# harp_timestamp_generator_Gen3.net
KiCad netlist of a schematic drawn in EAGLE
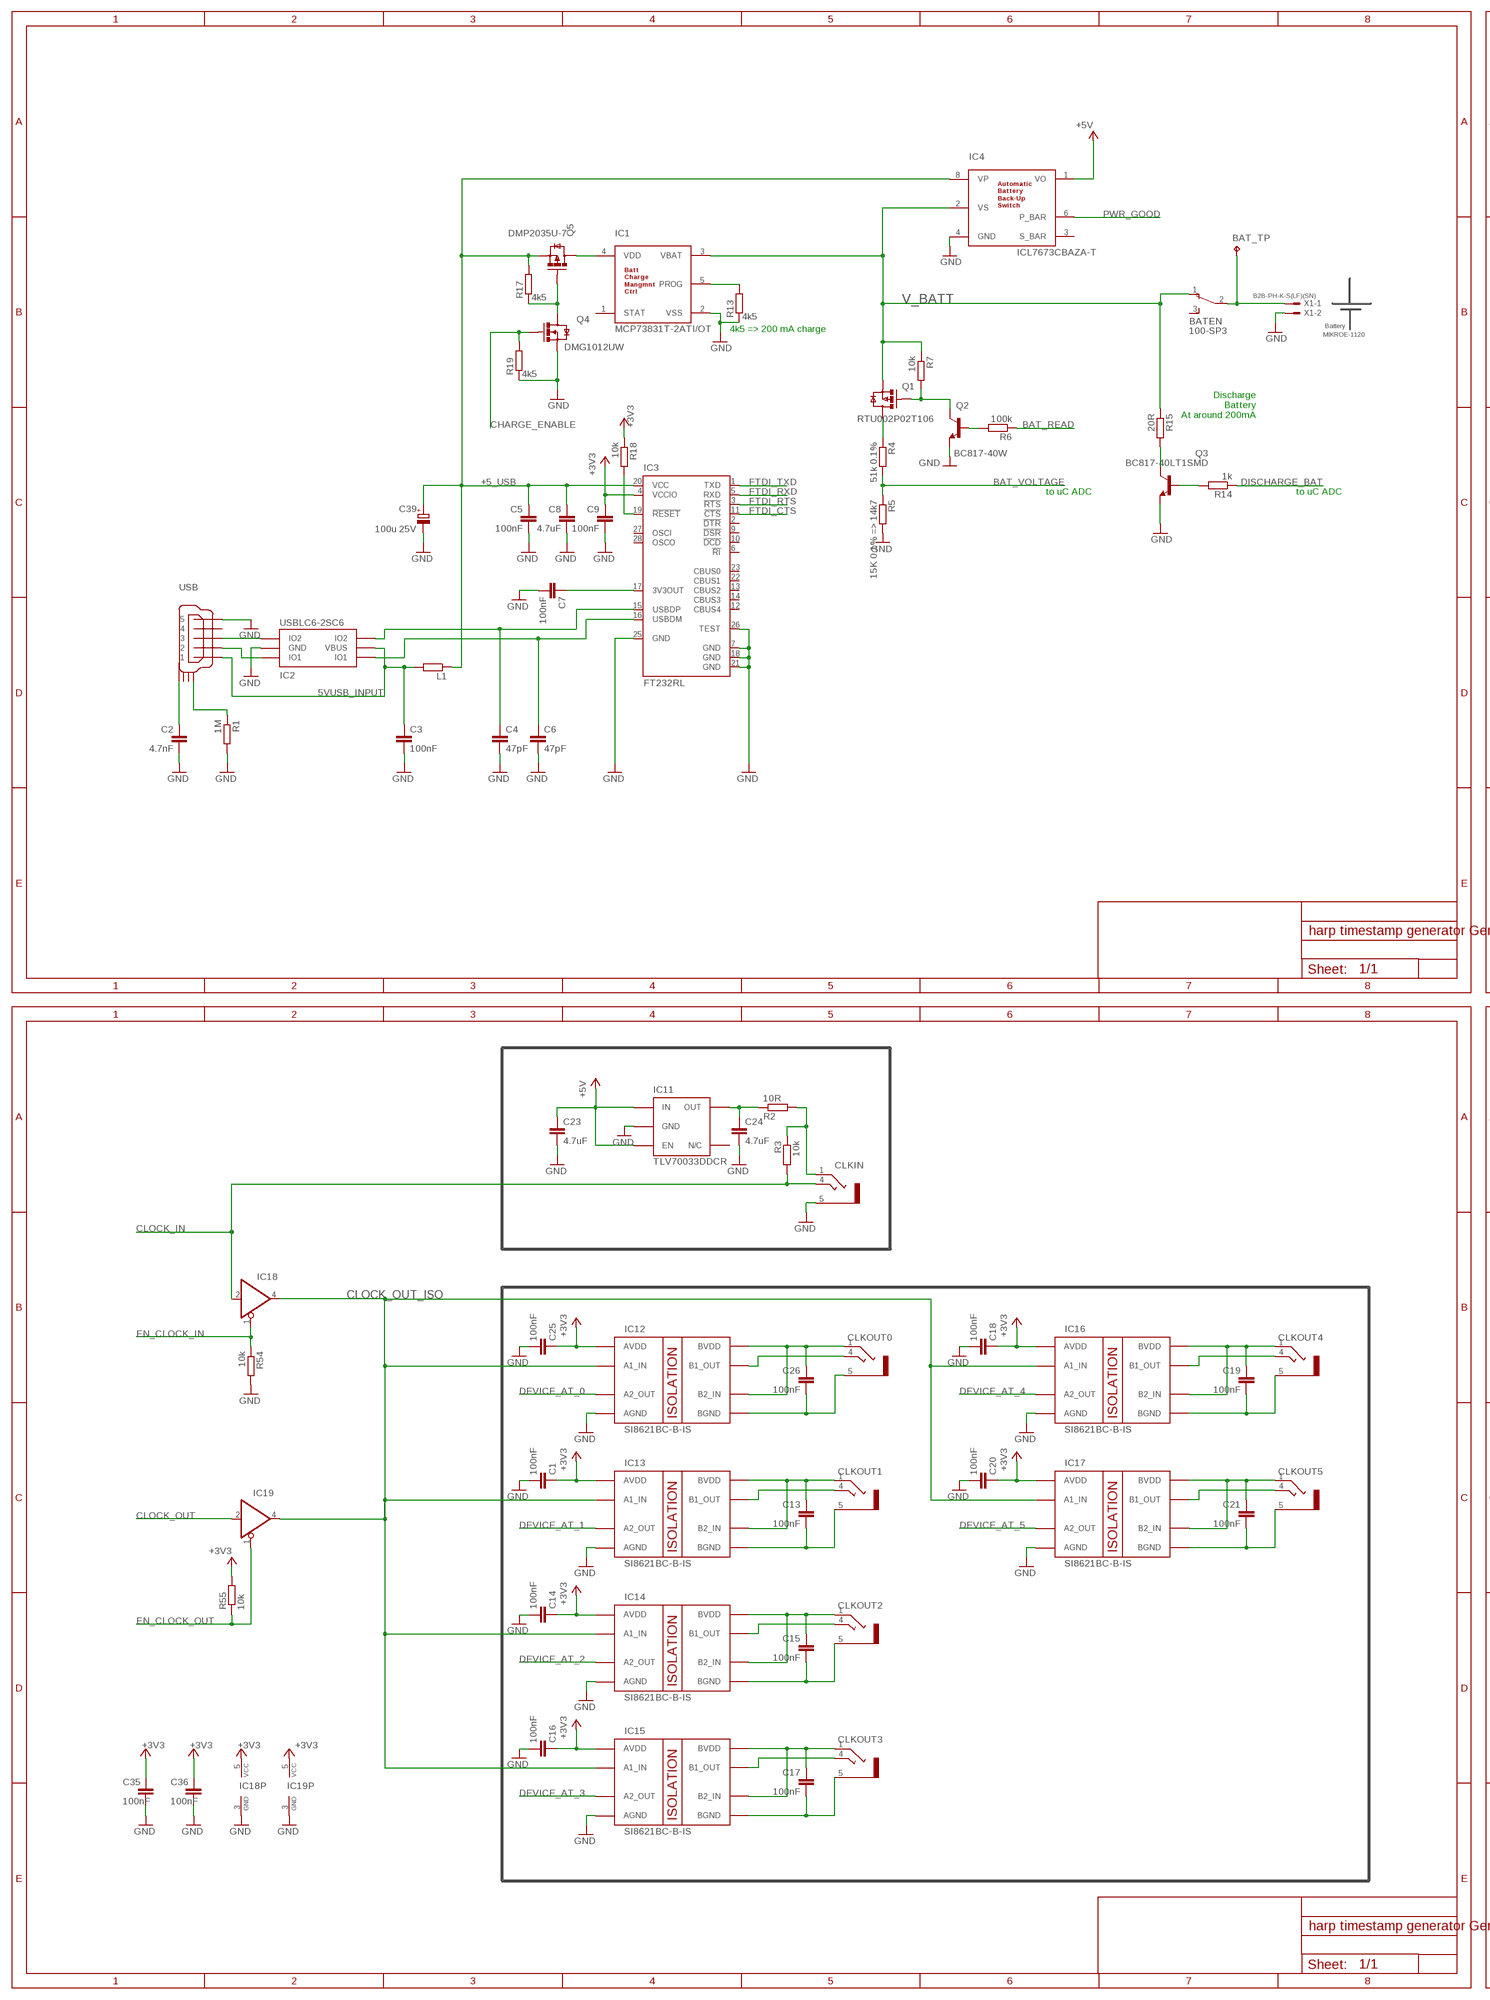
[diagram p0: schematic, sheet 1, part 1 of 2]
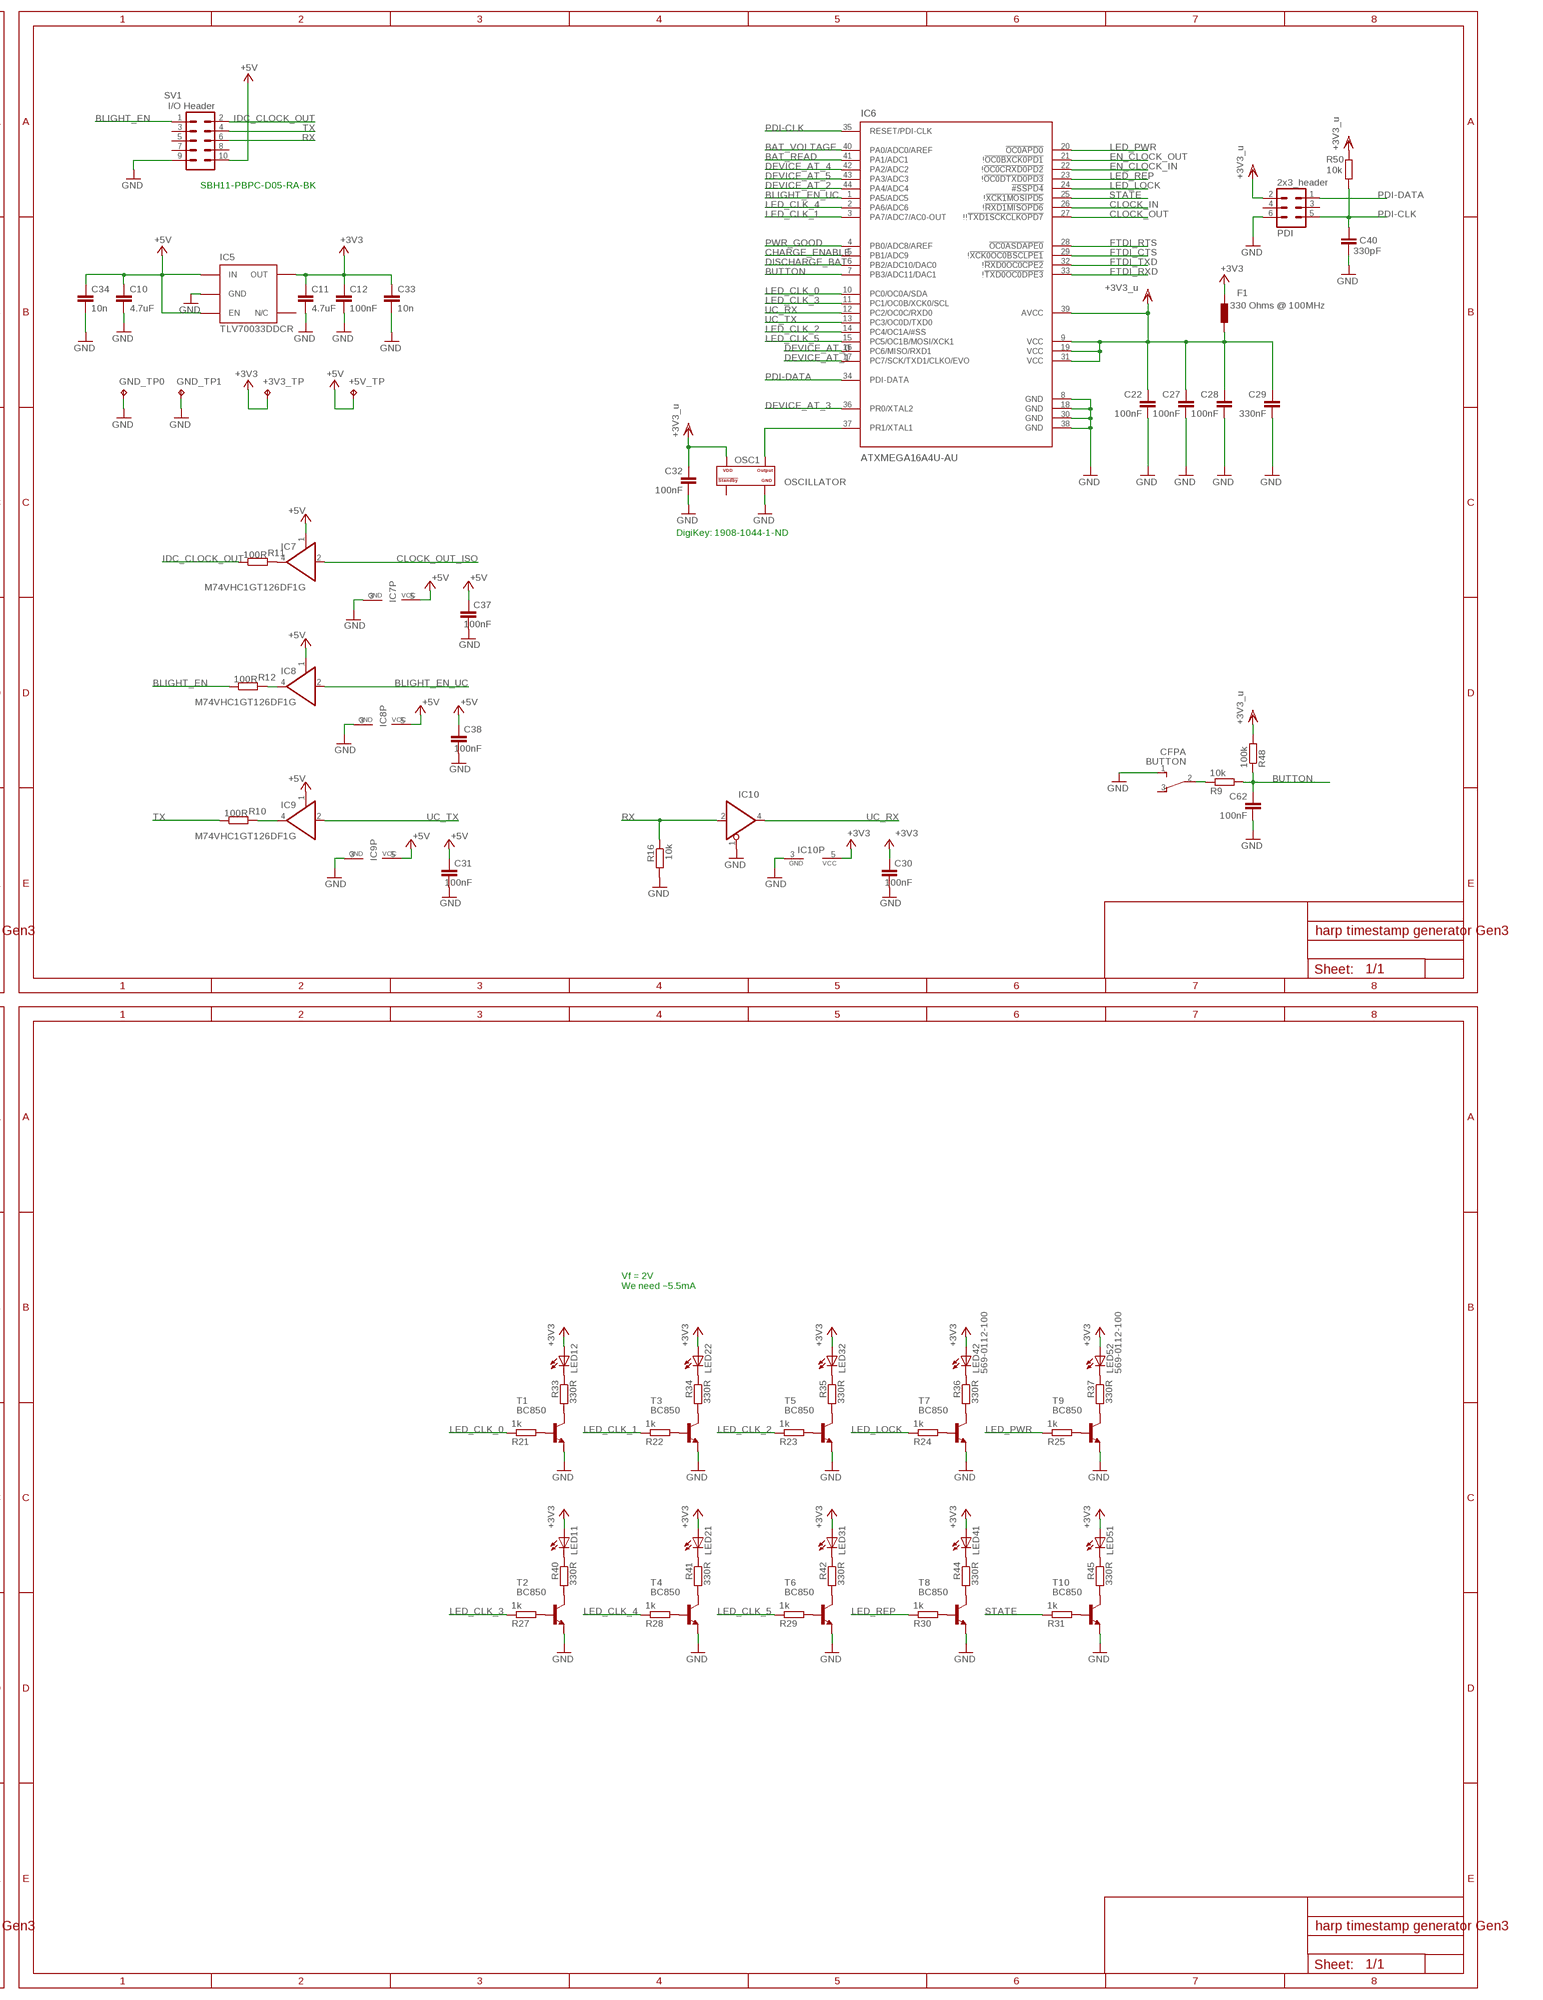
[diagram p1: schematic, sheet 1, part 2 of 2]

(export (version "E")
  (design (tool "Eeschema 10.0.6"))
  (components
    (comp (ref "+3V3_TP")
      (value "TPPAD1-13")
      (footprint "eagle-import:P1-13")
      (fields (field (name "MPN") "n.a."))
      (libsource (lib "eagle-import") (part "TPPAD1-13"))
    )
    (comp (ref "+5V_TP")
      (value "TPPAD1-13")
      (footprint "eagle-import:P1-13")
      (fields (field (name "MPN") "n.a."))
      (libsource (lib "eagle-import") (part "TPPAD1-13"))
    )
    (comp (ref "BATEN")
      (value "100-SP3")
      (footprint "eagle-import:2M1-SP1-T2-B4-M6RE")
      (libsource (lib "eagle-import") (part "SPDT_2M-WITHOFF"))
    )
    (comp (ref "BAT_TP")
      (value "TPPAD1-13")
      (footprint "eagle-import:P1-13")
      (fields (field (name "MPN") "n.a."))
      (libsource (lib "eagle-import") (part "TPPAD1-13"))
    )
    (comp (ref "BUTTON")
      (value "CFPA")
      (footprint "eagle-import:CFPA")
      (fields (field (name "MPN") "CFPA-1FB4-A2T"))
      (libsource (lib "eagle-import") (part "harp timestamp generator_SPDT_CFPA"))
    )
    (comp (ref "C1")
      (value "100nF")
      (footprint "eagle-import:C0402")
      (fields (field (name "MPN") "CGA2B3X7R1H104K050BB"))
      (libsource (lib "eagle-import") (part "C-EUC0402"))
    )
    (comp (ref "C2")
      (value "4.7nF")
      (footprint "eagle-import:C0402")
      (fields (field (name "MPN") "UMK105B7472KV-F"))
      (libsource (lib "eagle-import") (part "C-EUC0402"))
    )
    (comp (ref "C3")
      (value "100nF")
      (footprint "eagle-import:C0402")
      (fields (field (name "MPN") "CGA2B3X7R1H104K050BB"))
      (libsource (lib "eagle-import") (part "C-EUC0402"))
    )
    (comp (ref "C4")
      (value "47pF")
      (footprint "eagle-import:C0402")
      (fields (field (name "MPN") "04025A470JAT2A"))
      (libsource (lib "eagle-import") (part "C-EUC0402"))
    )
    (comp (ref "C5")
      (value "100nF")
      (footprint "eagle-import:C0402")
      (fields (field (name "MPN") "CGA2B3X7R1H104K050BB"))
      (libsource (lib "eagle-import") (part "C-EUC0402"))
    )
    (comp (ref "C6")
      (value "47pF")
      (footprint "eagle-import:C0402")
      (fields (field (name "MPN") "04025A470JAT2A"))
      (libsource (lib "eagle-import") (part "C-EUC0402"))
    )
    (comp (ref "C7")
      (value "100nF")
      (footprint "eagle-import:C0402")
      (fields (field (name "MPN") "CGA2B3X7R1H104K050BB"))
      (libsource (lib "eagle-import") (part "C-EUC0402"))
    )
    (comp (ref "C8")
      (value "4.7uF")
      (footprint "eagle-import:C0603")
      (fields (field (name "MPN") "EMK107ABJ475KA-T"))
      (libsource (lib "eagle-import") (part "C-EUC0603"))
    )
    (comp (ref "C9")
      (value "100nF")
      (footprint "eagle-import:C0402")
      (fields (field (name "MPN") "CGA2B3X7R1H104K050BB"))
      (libsource (lib "eagle-import") (part "C-EUC0402"))
    )
    (comp (ref "C10")
      (value "4.7uF")
      (footprint "eagle-import:C0603")
      (fields (field (name "MPN") "EMK107ABJ475KA-T"))
      (libsource (lib "eagle-import") (part "C-EUC0603"))
    )
    (comp (ref "C11")
      (value "4.7uF")
      (footprint "eagle-import:C0603")
      (fields (field (name "MPN") "EMK107ABJ475KA-T"))
      (libsource (lib "eagle-import") (part "C-EUC0603"))
    )
    (comp (ref "C12")
      (value "100nF")
      (footprint "eagle-import:C0402")
      (fields (field (name "MPN") "CGA2B3X7R1H104K050BB"))
      (libsource (lib "eagle-import") (part "C-EUC0402"))
    )
    (comp (ref "C13")
      (value "100nF")
      (footprint "eagle-import:C0402")
      (fields (field (name "MPN") "CGA2B3X7R1H104K050BB"))
      (libsource (lib "eagle-import") (part "C-EUC0402"))
    )
    (comp (ref "C14")
      (value "100nF")
      (footprint "eagle-import:C0402")
      (fields (field (name "MPN") "CGA2B3X7R1H104K050BB"))
      (libsource (lib "eagle-import") (part "C-EUC0402"))
    )
    (comp (ref "C15")
      (value "100nF")
      (footprint "eagle-import:C0402")
      (fields (field (name "MPN") "CGA2B3X7R1H104K050BB"))
      (libsource (lib "eagle-import") (part "C-EUC0402"))
    )
    (comp (ref "C16")
      (value "100nF")
      (footprint "eagle-import:C0402")
      (fields (field (name "MPN") "CGA2B3X7R1H104K050BB"))
      (libsource (lib "eagle-import") (part "C-EUC0402"))
    )
    (comp (ref "C17")
      (value "100nF")
      (footprint "eagle-import:C0402")
      (fields (field (name "MPN") "CGA2B3X7R1H104K050BB"))
      (libsource (lib "eagle-import") (part "C-EUC0402"))
    )
    (comp (ref "C18")
      (value "100nF")
      (footprint "eagle-import:C0402")
      (fields (field (name "MPN") "CGA2B3X7R1H104K050BB"))
      (libsource (lib "eagle-import") (part "C-EUC0402"))
    )
    (comp (ref "C19")
      (value "100nF")
      (footprint "eagle-import:C0402")
      (fields (field (name "MPN") "CGA2B3X7R1H104K050BB"))
      (libsource (lib "eagle-import") (part "C-EUC0402"))
    )
    (comp (ref "C20")
      (value "100nF")
      (footprint "eagle-import:C0402")
      (fields (field (name "MPN") "CGA2B3X7R1H104K050BB"))
      (libsource (lib "eagle-import") (part "C-EUC0402"))
    )
    (comp (ref "C21")
      (value "100nF")
      (footprint "eagle-import:C0402")
      (fields (field (name "MPN") "CGA2B3X7R1H104K050BB"))
      (libsource (lib "eagle-import") (part "C-EUC0402"))
    )
    (comp (ref "C22")
      (value "100nF")
      (footprint "eagle-import:C0402")
      (fields (field (name "MPN") "CGA2B3X7R1H104K050BB"))
      (libsource (lib "eagle-import") (part "C-EUC0402"))
    )
    (comp (ref "C23")
      (value "4.7uF")
      (footprint "eagle-import:C0603")
      (fields (field (name "MPN") "EMK107ABJ475KA-T"))
      (libsource (lib "eagle-import") (part "C-EUC0603"))
    )
    (comp (ref "C24")
      (value "4.7uF")
      (footprint "eagle-import:C0603")
      (fields (field (name "MPN") "EMK107ABJ475KA-T"))
      (libsource (lib "eagle-import") (part "C-EUC0603"))
    )
    (comp (ref "C25")
      (value "100nF")
      (footprint "eagle-import:C0402")
      (fields (field (name "MPN") "CGA2B3X7R1H104K050BB"))
      (libsource (lib "eagle-import") (part "C-EUC0402"))
    )
    (comp (ref "C26")
      (value "100nF")
      (footprint "eagle-import:C0402")
      (fields (field (name "MPN") "CGA2B3X7R1H104K050BB"))
      (libsource (lib "eagle-import") (part "C-EUC0402"))
    )
    (comp (ref "C27")
      (value "100nF")
      (footprint "eagle-import:C0402")
      (fields (field (name "MPN") "CGA2B3X7R1H104K050BB"))
      (libsource (lib "eagle-import") (part "C-EUC0402"))
    )
    (comp (ref "C28")
      (value "100nF")
      (footprint "eagle-import:C0402")
      (fields (field (name "MPN") "CGA2B3X7R1H104K050BB"))
      (libsource (lib "eagle-import") (part "C-EUC0402"))
    )
    (comp (ref "C29")
      (value "330nF")
      (footprint "eagle-import:C0402")
      (fields (field (name "MPN") "GRM155R61A334KE15D"))
      (libsource (lib "eagle-import") (part "C-EUC0402"))
    )
    (comp (ref "C30")
      (value "100nF")
      (footprint "eagle-import:C0402")
      (fields (field (name "MPN") "CGA2B3X7R1H104K050BB"))
      (libsource (lib "eagle-import") (part "C-EUC0402"))
    )
    (comp (ref "C31")
      (value "100nF")
      (footprint "eagle-import:C0402")
      (fields (field (name "MPN") "CGA2B3X7R1H104K050BB"))
      (libsource (lib "eagle-import") (part "C-EUC0402"))
    )
    (comp (ref "C32")
      (value "100nF")
      (footprint "eagle-import:C0402")
      (fields (field (name "MPN") "CGA2B3X7R1H104K050BB"))
      (libsource (lib "eagle-import") (part "C-EUC0402"))
    )
    (comp (ref "C33")
      (value "10n")
      (footprint "eagle-import:C0402")
      (fields (field (name "MPN") "CL05B103KB5NNNC"))
      (libsource (lib "eagle-import") (part "C-EUC0402"))
    )
    (comp (ref "C34")
      (value "10n")
      (footprint "eagle-import:C0402")
      (fields (field (name "MPN") "CL05B103KB5NNNC"))
      (libsource (lib "eagle-import") (part "C-EUC0402"))
    )
    (comp (ref "C35")
      (value "100nF")
      (footprint "eagle-import:C0402")
      (fields (field (name "MPN") "CGA2B3X7R1H104K050BB"))
      (libsource (lib "eagle-import") (part "C-EUC0402"))
    )
    (comp (ref "C36")
      (value "100nF")
      (footprint "eagle-import:C0402")
      (fields (field (name "MPN") "CGA2B3X7R1H104K050BB"))
      (libsource (lib "eagle-import") (part "C-EUC0402"))
    )
    (comp (ref "C37")
      (value "100nF")
      (footprint "eagle-import:C0402")
      (fields (field (name "MPN") "CGA2B3X7R1H104K050BB"))
      (libsource (lib "eagle-import") (part "C-EUC0402"))
    )
    (comp (ref "C38")
      (value "100nF")
      (footprint "eagle-import:C0402")
      (fields (field (name "MPN") "CGA2B3X7R1H104K050BB"))
      (libsource (lib "eagle-import") (part "C-EUC0402"))
    )
    (comp (ref "C39")
      (value "100u 25V")
      (footprint "eagle-import:TT2D6")
      (fields (field (name "MPN") "EEUFM1E101B"))
      (libsource (lib "eagle-import") (part "CPOL-EUTT2D6"))
    )
    (comp (ref "C40")
      (value "330pF")
      (footprint "eagle-import:C0402")
      (fields (field (name "MPN") "C0402C331J5GACTU"))
      (libsource (lib "eagle-import") (part "C-EUC0402"))
    )
    (comp (ref "C62")
      (value "100nF")
      (footprint "eagle-import:C0402")
      (fields (field (name "MPN") "CGA2B3X7R1H104K050BB"))
      (libsource (lib "eagle-import") (part "C-EUC0402"))
    )
    (comp (ref "CLKIN")
      (value "CLCK_JACK")
      (footprint "eagle-import:35RASMT2BHNTRX")
      (fields (field (name "MPN") "35RASMT2BHNTRX"))
      (libsource (lib "eagle-import") (part "STEREO_JACK"))
    )
    (comp (ref "CLKOUT0")
      (value "CLCK_JACK")
      (footprint "eagle-import:35RASMT2BHNTRX")
      (fields (field (name "MPN") "35RASMT2BHNTRX"))
      (libsource (lib "eagle-import") (part "STEREO_JACK"))
    )
    (comp (ref "CLKOUT1")
      (value "CLCK_JACK")
      (footprint "eagle-import:35RASMT2BHNTRX")
      (fields (field (name "MPN") "35RASMT2BHNTRX"))
      (libsource (lib "eagle-import") (part "STEREO_JACK"))
    )
    (comp (ref "CLKOUT2")
      (value "CLCK_JACK")
      (footprint "eagle-import:35RASMT2BHNTRX")
      (fields (field (name "MPN") "35RASMT2BHNTRX"))
      (libsource (lib "eagle-import") (part "STEREO_JACK"))
    )
    (comp (ref "CLKOUT3")
      (value "CLCK_JACK")
      (footprint "eagle-import:35RASMT2BHNTRX")
      (fields (field (name "MPN") "35RASMT2BHNTRX"))
      (libsource (lib "eagle-import") (part "STEREO_JACK"))
    )
    (comp (ref "CLKOUT4")
      (value "CLCK_JACK")
      (footprint "eagle-import:35RASMT2BHNTRX")
      (fields (field (name "MPN") "35RASMT2BHNTRX"))
      (libsource (lib "eagle-import") (part "STEREO_JACK"))
    )
    (comp (ref "CLKOUT5")
      (value "CLCK_JACK")
      (footprint "eagle-import:35RASMT2BHNTRX")
      (fields (field (name "MPN") "35RASMT2BHNTRX"))
      (libsource (lib "eagle-import") (part "STEREO_JACK"))
    )
    (comp (ref "F1")
      (value "330 Ohms @ 100MHz")
      (footprint "eagle-import:R0603")
      (fields (field (name "MPN") "BLM18SG331TN1D"))
      (libsource (lib "eagle-import") (part "BLM15HF0603"))
    )
    (comp (ref "GND_TP0")
      (value "TPPAD1-13")
      (footprint "eagle-import:P1-13")
      (fields (field (name "MPN") "n.a."))
      (libsource (lib "eagle-import") (part "TPPAD1-13"))
    )
    (comp (ref "GND_TP1")
      (value "TPPAD1-13")
      (footprint "eagle-import:P1-13")
      (fields (field (name "MPN") "n.a."))
      (libsource (lib "eagle-import") (part "TPPAD1-13"))
    )
    (comp (ref "IC1")
      (value "MCP73831T-2ATI/OT")
      (footprint "eagle-import:TSOT23-5")
      (libsource (lib "eagle-import") (part "MCP73831T-2ATI/OT"))
    )
    (comp (ref "IC2")
      (value "USBLC6-2SC6")
      (footprint "eagle-import:SOT23-6L")
      (libsource (lib "eagle-import") (part "USBLC6-2"))
    )
    (comp (ref "IC3")
      (value "FT232RL")
      (footprint "eagle-import:SSOP28")
      (fields (field (name "MPN") "FT232RL-REEL"))
      (libsource (lib "eagle-import") (part "FT232RL"))
    )
    (comp (ref "IC4")
      (value "ICL7673CBAZA-T")
      (footprint "eagle-import:SOIC8")
      (libsource (lib "eagle-import") (part "ICL7673CBAZA-T"))
    )
    (comp (ref "IC5")
      (value "TLV70033DDCR")
      (footprint "eagle-import:TSOT23-5")
      (libsource (lib "eagle-import") (part "TLV700XX"))
    )
    (comp (ref "IC6")
      (value "ATXMEGA16A4U-AU")
      (footprint "eagle-import:QFP80P1200X1200X120-44N")
      (libsource (lib "eagle-import") (part "AT-XMEGA-XXA4-AU"))
    )
    (comp (ref "IC7")
      (value "M74VHC1GT126DF1G")
      (footprint "eagle-import:SC70-5")
      (fields (field (name "MPN") "M74VHC1GT126DF1G"))
      (libsource (lib "eagle-import") (part "741G126DCKAHC"))
    )
    (comp (ref "IC8")
      (value "M74VHC1GT126DF1G")
      (footprint "eagle-import:SC70-5")
      (fields (field (name "MPN") "M74VHC1GT126DF1G"))
      (libsource (lib "eagle-import") (part "741G126DCKAHC"))
    )
    (comp (ref "IC9")
      (value "M74VHC1GT126DF1G")
      (footprint "eagle-import:SC70-5")
      (fields (field (name "MPN") "M74VHC1GT126DF1G"))
      (libsource (lib "eagle-import") (part "741G126DCKAHC"))
    )
    (comp (ref "IC10")
      (value "SN74LVC1G125DBVT")
      (footprint "eagle-import:SOT23-5")
      (fields (field (name "MPN") "SN74LVC1G125DBVT"))
      (libsource (lib "eagle-import") (part "741G125DBVAHC"))
    )
    (comp (ref "IC11")
      (value "TLV70033DDCR")
      (footprint "eagle-import:TSOT23-5")
      (libsource (lib "eagle-import") (part "TLV700XX"))
    )
    (comp (ref "IC12")
      (value "SI8621BC-B-IS")
      (footprint "eagle-import:SOIC8")
      (fields (field (name "MPN") "Si8621BC-B-IS"))
      (libsource (lib "eagle-import") (part "SI8621BC-B-IS"))
    )
    (comp (ref "IC13")
      (value "SI8621BC-B-IS")
      (footprint "eagle-import:SOIC8")
      (fields (field (name "MPN") "Si8621BC-B-IS"))
      (libsource (lib "eagle-import") (part "SI8621BC-B-IS"))
    )
    (comp (ref "IC14")
      (value "SI8621BC-B-IS")
      (footprint "eagle-import:SOIC8")
      (fields (field (name "MPN") "Si8621BC-B-IS"))
      (libsource (lib "eagle-import") (part "SI8621BC-B-IS"))
    )
    (comp (ref "IC15")
      (value "SI8621BC-B-IS")
      (footprint "eagle-import:SOIC8")
      (fields (field (name "MPN") "Si8621BC-B-IS"))
      (libsource (lib "eagle-import") (part "SI8621BC-B-IS"))
    )
    (comp (ref "IC16")
      (value "SI8621BC-B-IS")
      (footprint "eagle-import:SOIC8")
      (fields (field (name "MPN") "Si8621BC-B-IS"))
      (libsource (lib "eagle-import") (part "SI8621BC-B-IS"))
    )
    (comp (ref "IC17")
      (value "SI8621BC-B-IS")
      (footprint "eagle-import:SOIC8")
      (fields (field (name "MPN") "Si8621BC-B-IS"))
      (libsource (lib "eagle-import") (part "SI8621BC-B-IS"))
    )
    (comp (ref "IC18")
      (value "SN74LVC1G125DBVT")
      (footprint "eagle-import:SOT23-5")
      (fields (field (name "MPN") "SN74LVC1G125DBVT"))
      (libsource (lib "eagle-import") (part "741G125DBVAHC"))
    )
    (comp (ref "IC19")
      (value "SN74LVC1G125DBVT")
      (footprint "eagle-import:SOT23-5")
      (fields (field (name "MPN") "SN74LVC1G125DBVT"))
      (libsource (lib "eagle-import") (part "741G125DBVAHC"))
    )
    (comp (ref "L1")
      (value "40R@100MHz")
      (footprint "eagle-import:R0805")
      (fields (field (name "MPN") "MI0805K400R-10"))
      (libsource (lib "eagle-import") (part "R-EU_R0805"))
    )
    (comp (ref "LED1")
      (value "569-0112-100")
      (footprint "eagle-import:569-011X-X00_LED_ARRAY")
      (fields (field (name "MPN") "5690-111-100F"))
      (libsource (lib "eagle-import") (part "LED_2X_VERTICAL"))
    )
    (comp (ref "LED2")
      (value "569-0112-100")
      (footprint "eagle-import:569-011X-X00_LED_ARRAY")
      (fields (field (name "MPN") "5690-111-100F"))
      (libsource (lib "eagle-import") (part "LED_2X_VERTICAL"))
    )
    (comp (ref "LED3")
      (value "569-0112-100")
      (footprint "eagle-import:569-011X-X00_LED_ARRAY")
      (fields (field (name "MPN") "5690-111-100F"))
      (libsource (lib "eagle-import") (part "LED_2X_VERTICAL"))
    )
    (comp (ref "LED4")
      (value "569-0112-100")
      (footprint "eagle-import:569-011X-X00_LED_ARRAY")
      (fields (field (name "MPN") "5690-111-100F"))
      (libsource (lib "eagle-import") (part "LED_2X_VERTICAL"))
    )
    (comp (ref "LED5")
      (value "569-0112-100")
      (footprint "eagle-import:569-011X-X00_LED_ARRAY")
      (fields (field (name "MPN") "5690-111-100F"))
      (libsource (lib "eagle-import") (part "LED_2X_VERTICAL"))
    )
    (comp (ref "OSC1")
      (value "OSCILLATOR")
      (footprint "eagle-import:OSCILLATOR_3.2X2.5")
      (fields (field (name "MPN") "O 32,0-JT32C-A-K-3,3-LF"))
      (libsource (lib "eagle-import") (part "OSCILLATOR"))
    )
    (comp (ref "PDI")
      (value "2x3_header")
      (footprint "eagle-import:MA03-2")
      (fields (field (name "MPN") "67996-206HLF"))
      (libsource (lib "eagle-import") (part "MA03-2"))
    )
    (comp (ref "Q1")
      (value "RTU002P02T106")
      (footprint "eagle-import:SOT323")
      (libsource (lib "eagle-import") (part "MOSFET-PCHANNEL-ROHM"))
    )
    (comp (ref "Q2")
      (value "BC817-40W")
      (footprint "eagle-import:SOT323-BEC")
      (fields (field (name "MPN") "BC817-40W,135"))
      (libsource (lib "eagle-import") (part "BC817"))
    )
    (comp (ref "Q3")
      (value "BC817-40LT1SMD")
      (footprint "eagle-import:SOT23-BEC")
      (fields (field (name "MPN") "SBC817-40LT1G"))
      (libsource (lib "eagle-import") (part "transistor-npn_398_BC817SMD-40LT1"))
    )
    (comp (ref "Q4")
      (value "DMG1012UW")
      (footprint "eagle-import:SOT323")
      (fields (field (name "MPN") "DMG1012UW-7"))
      (libsource (lib "eagle-import") (part "DMG1012UW"))
    )
    (comp (ref "Q5")
      (value "DMP2035U-7")
      (footprint "eagle-import:SOT323")
      (libsource (lib "eagle-import") (part "DMP2035U-7"))
    )
    (comp (ref "R1")
      (value "1M")
      (footprint "eagle-import:R0402")
      (fields (field (name "MPN") "CRCW04021M00FKEDC"))
      (libsource (lib "eagle-import") (part "R-EU_R0402"))
    )
    (comp (ref "R2")
      (value "10R")
      (footprint "eagle-import:R0402")
      (fields (field (name "MPN") "CRCW040210R0FKEDHP"))
      (libsource (lib "eagle-import") (part "R-EU_R0402"))
    )
    (comp (ref "R3")
      (value "10k")
      (footprint "eagle-import:R0402")
      (fields (field (name "MPN") "CRCW040210K0FKEDC"))
      (libsource (lib "eagle-import") (part "R-EU_R0402"))
    )
    (comp (ref "R4")
      (value "51k 0.1%")
      (footprint "eagle-import:R0402")
      (fields (field (name "MPN") "ERA-2AEB513X"))
      (libsource (lib "eagle-import") (part "R-EU_R0402"))
    )
    (comp (ref "R5")
      (value "15K 0.1% => 14k7")
      (footprint "eagle-import:R0402")
      (fields (field (name "MPN") "RT0402BRD0714K7L"))
      (libsource (lib "eagle-import") (part "R-EU_R0402"))
    )
    (comp (ref "R6")
      (value "100k")
      (footprint "eagle-import:R0402")
      (fields (field (name "MPN") "ERJ-2RHD1002X"))
      (libsource (lib "eagle-import") (part "R-EU_R0402"))
    )
    (comp (ref "R7")
      (value "10k")
      (footprint "eagle-import:R0402")
      (fields (field (name "MPN") "CRCW040210K0FKEDC"))
      (libsource (lib "eagle-import") (part "R-EU_R0402"))
    )
    (comp (ref "R9")
      (value "10k")
      (footprint "eagle-import:R0402")
      (fields (field (name "MPN") "CRCW040210K0FKEDC"))
      (libsource (lib "eagle-import") (part "R-EU_R0402"))
    )
    (comp (ref "R10")
      (value "100R")
      (footprint "eagle-import:R0603")
      (fields (field (name "MPN") "RT0603DRD07100RL"))
      (libsource (lib "eagle-import") (part "R-EU_R0603"))
    )
    (comp (ref "R11")
      (value "100R")
      (footprint "eagle-import:R0603")
      (fields (field (name "MPN") "RT0603DRD07100RL"))
      (libsource (lib "eagle-import") (part "R-EU_R0603"))
    )
    (comp (ref "R12")
      (value "100R")
      (footprint "eagle-import:R0603")
      (fields (field (name "MPN") "RT0603DRD07100RL"))
      (libsource (lib "eagle-import") (part "R-EU_R0603"))
    )
    (comp (ref "R13")
      (value "4k5")
      (footprint "eagle-import:R0402")
      (fields (field (name "MPN") "RT0402BRD074K53L"))
      (libsource (lib "eagle-import") (part "R-EU_R0402"))
    )
    (comp (ref "R14")
      (value "1k")
      (footprint "eagle-import:R0402")
      (fields (field (name "MPN") "CRCW040210K0FKEDC"))
      (libsource (lib "eagle-import") (part "R-EU_R0402"))
    )
    (comp (ref "R15")
      (value "20R")
      (footprint "eagle-import:R2512")
      (fields (field (name "MPN") "RCP2512W25R0GEB"))
      (libsource (lib "eagle-import") (part "R-EU_R2512"))
    )
    (comp (ref "R16")
      (value "10k")
      (footprint "eagle-import:R0402")
      (fields (field (name "MPN") "CRCW040210K0FKEDC"))
      (libsource (lib "eagle-import") (part "R-EU_R0402"))
    )
    (comp (ref "R17")
      (value "4k5")
      (footprint "eagle-import:R0402")
      (fields (field (name "MPN") "RT0402BRD074K53L"))
      (libsource (lib "eagle-import") (part "R-EU_R0402"))
    )
    (comp (ref "R18")
      (value "10k")
      (footprint "eagle-import:R0402")
      (fields (field (name "MPN") "CRCW040210K0FKEDC"))
      (libsource (lib "eagle-import") (part "R-EU_R0402"))
    )
    (comp (ref "R19")
      (value "4k5")
      (footprint "eagle-import:R0402")
      (fields (field (name "MPN") "RT0402BRD074K53L"))
      (libsource (lib "eagle-import") (part "R-EU_R0402"))
    )
    (comp (ref "R21")
      (value "1k")
      (footprint "eagle-import:R0402")
      (fields (field (name "MPN") "CRCW04021K00FKEDHP"))
      (libsource (lib "eagle-import") (part "R-EU_R0402"))
    )
    (comp (ref "R22")
      (value "1k")
      (footprint "eagle-import:R0402")
      (fields (field (name "MPN") "CRCW04021K00FKEDHP"))
      (libsource (lib "eagle-import") (part "R-EU_R0402"))
    )
    (comp (ref "R23")
      (value "1k")
      (footprint "eagle-import:R0402")
      (fields (field (name "MPN") "CRCW04021K00FKEDHP"))
      (libsource (lib "eagle-import") (part "R-EU_R0402"))
    )
    (comp (ref "R24")
      (value "1k")
      (footprint "eagle-import:R0402")
      (fields (field (name "MPN") "CRCW04021K00FKEDHP"))
      (libsource (lib "eagle-import") (part "R-EU_R0402"))
    )
    (comp (ref "R25")
      (value "1k")
      (footprint "eagle-import:R0402")
      (fields (field (name "MPN") "CRCW04021K00FKEDHP"))
      (libsource (lib "eagle-import") (part "R-EU_R0402"))
    )
    (comp (ref "R27")
      (value "1k")
      (footprint "eagle-import:R0402")
      (fields (field (name "MPN") "CRCW04021K00FKEDHP"))
      (libsource (lib "eagle-import") (part "R-EU_R0402"))
    )
    (comp (ref "R28")
      (value "1k")
      (footprint "eagle-import:R0402")
      (fields (field (name "MPN") "CRCW04021K00FKEDHP"))
      (libsource (lib "eagle-import") (part "R-EU_R0402"))
    )
    (comp (ref "R29")
      (value "1k")
      (footprint "eagle-import:R0402")
      (fields (field (name "MPN") "CRCW04021K00FKEDHP"))
      (libsource (lib "eagle-import") (part "R-EU_R0402"))
    )
    (comp (ref "R30")
      (value "1k")
      (footprint "eagle-import:R0402")
      (fields (field (name "MPN") "CRCW04021K00FKEDHP"))
      (libsource (lib "eagle-import") (part "R-EU_R0402"))
    )
    (comp (ref "R31")
      (value "1k")
      (footprint "eagle-import:R0402")
      (fields (field (name "MPN") "CRCW04021K00FKEDHP"))
      (libsource (lib "eagle-import") (part "R-EU_R0402"))
    )
    (comp (ref "R33")
      (value "330R")
      (footprint "eagle-import:R0402")
      (fields (field (name "MPN") "RC0402FR-07330RL "))
      (libsource (lib "eagle-import") (part "R-EU_R0402"))
    )
    (comp (ref "R34")
      (value "330R")
      (footprint "eagle-import:R0402")
      (fields (field (name "MPN") "RC0402FR-07330RL "))
      (libsource (lib "eagle-import") (part "R-EU_R0402"))
    )
    (comp (ref "R35")
      (value "330R")
      (footprint "eagle-import:R0402")
      (fields (field (name "MPN") "RC0402FR-07330RL "))
      (libsource (lib "eagle-import") (part "R-EU_R0402"))
    )
    (comp (ref "R36")
      (value "330R")
      (footprint "eagle-import:R0402")
      (fields (field (name "MPN") "RC0402FR-07330RL "))
      (libsource (lib "eagle-import") (part "R-EU_R0402"))
    )
    (comp (ref "R37")
      (value "330R")
      (footprint "eagle-import:R0402")
      (fields (field (name "MPN") "RC0402FR-07330RL "))
      (libsource (lib "eagle-import") (part "R-EU_R0402"))
    )
    (comp (ref "R40")
      (value "330R")
      (footprint "eagle-import:R0402")
      (fields (field (name "MPN") "RC0402FR-07330RL "))
      (libsource (lib "eagle-import") (part "R-EU_R0402"))
    )
    (comp (ref "R41")
      (value "330R")
      (footprint "eagle-import:R0402")
      (fields (field (name "MPN") "RC0402FR-07330RL "))
      (libsource (lib "eagle-import") (part "R-EU_R0402"))
    )
    (comp (ref "R42")
      (value "330R")
      (footprint "eagle-import:R0402")
      (fields (field (name "MPN") "RC0402FR-07330RL "))
      (libsource (lib "eagle-import") (part "R-EU_R0402"))
    )
    (comp (ref "R44")
      (value "330R")
      (footprint "eagle-import:R0402")
      (fields (field (name "MPN") "RC0402FR-07330RL "))
      (libsource (lib "eagle-import") (part "R-EU_R0402"))
    )
    (comp (ref "R45")
      (value "330R")
      (footprint "eagle-import:R0402")
      (fields (field (name "MPN") "RC0402FR-07330RL "))
      (libsource (lib "eagle-import") (part "R-EU_R0402"))
    )
    (comp (ref "R48")
      (value "100k")
      (footprint "eagle-import:R0402")
      (fields (field (name "MPN") "ERJ-2RHD1002X"))
      (libsource (lib "eagle-import") (part "R-EU_R0402"))
    )
    (comp (ref "R50")
      (value "10k")
      (footprint "eagle-import:R0402")
      (fields (field (name "MPN") "CRCW040210K0FKED"))
      (libsource (lib "eagle-import") (part "R-EU_R0402"))
    )
    (comp (ref "R54")
      (value "10k")
      (footprint "eagle-import:R0402")
      (fields (field (name "MPN") "CRCW04021K00FKEDHP"))
      (libsource (lib "eagle-import") (part "R-EU_R0402"))
    )
    (comp (ref "R55")
      (value "10k")
      (footprint "eagle-import:R0402")
      (fields (field (name "MPN") "CRCW04021K00FKEDHP"))
      (libsource (lib "eagle-import") (part "R-EU_R0402"))
    )
    (comp (ref "SV1")
      (value "I/O Header")
      (footprint "eagle-import:ML10L")
      (fields (field (name "MPN") "SBH11-PBPC-D05-RA-BK"))
      (libsource (lib "eagle-import") (part "ML10L"))
    )
    (comp (ref "T1")
      (value "BC850")
      (footprint "eagle-import:SOT23")
      (fields (field (name "MPN") "BC850C,215"))
      (libsource (lib "eagle-import") (part "BC850"))
    )
    (comp (ref "T2")
      (value "BC850")
      (footprint "eagle-import:SOT23")
      (fields (field (name "MPN") "BC850C,215"))
      (libsource (lib "eagle-import") (part "BC850"))
    )
    (comp (ref "T3")
      (value "BC850")
      (footprint "eagle-import:SOT23")
      (fields (field (name "MPN") "BC850C,215"))
      (libsource (lib "eagle-import") (part "BC850"))
    )
    (comp (ref "T4")
      (value "BC850")
      (footprint "eagle-import:SOT23")
      (fields (field (name "MPN") "BC850C,215"))
      (libsource (lib "eagle-import") (part "BC850"))
    )
    (comp (ref "T5")
      (value "BC850")
      (footprint "eagle-import:SOT23")
      (fields (field (name "MPN") "BC850C,215"))
      (libsource (lib "eagle-import") (part "BC850"))
    )
    (comp (ref "T6")
      (value "BC850")
      (footprint "eagle-import:SOT23")
      (fields (field (name "MPN") "BC850C,215"))
      (libsource (lib "eagle-import") (part "BC850"))
    )
    (comp (ref "T7")
      (value "BC850")
      (footprint "eagle-import:SOT23")
      (fields (field (name "MPN") "BC850C,215"))
      (libsource (lib "eagle-import") (part "BC850"))
    )
    (comp (ref "T8")
      (value "BC850")
      (footprint "eagle-import:SOT23")
      (fields (field (name "MPN") "BC850C,215"))
      (libsource (lib "eagle-import") (part "BC850"))
    )
    (comp (ref "T9")
      (value "BC850")
      (footprint "eagle-import:SOT23")
      (fields (field (name "MPN") "BC850C,215"))
      (libsource (lib "eagle-import") (part "BC850"))
    )
    (comp (ref "T10")
      (value "BC850")
      (footprint "eagle-import:SOT23")
      (fields (field (name "MPN") "BC850C,215"))
      (libsource (lib "eagle-import") (part "BC850"))
    )
    (comp (ref "USB")
      (value "mini USB")
      (footprint "eagle-import:240-0002-1")
      (fields (field (name "MPN") "UX60-MB-5S8"))
      (libsource (lib "eagle-import") (part "USB_MINI_B"))
    )
    (comp (ref "X1")
      (value "B2B-PH-K-S(LF)(SN)")
      (footprint "eagle-import:JST-XH-02-PACKAGE-ROUND-PAD")
      (libsource (lib "eagle-import") (part "JST-XH-02-PIN-ROUND-PAD"))
    )
  )
  (nets
    (net (code "1") (name "+3V3") (class "Default")
      (node (ref "+3V3_TP") (pin "TP") (pinfunction "TP_TP") (pintype "input"))
      (node (ref "C1") (pin "1") (pinfunction "1_1") (pintype "passive"))
      (node (ref "C11") (pin "1") (pinfunction "1_1") (pintype "passive"))
      (node (ref "C12") (pin "1") (pinfunction "1_1") (pintype "passive"))
      (node (ref "C14") (pin "1") (pinfunction "1_1") (pintype "passive"))
      (node (ref "C16") (pin "1") (pinfunction "1_1") (pintype "passive"))
      (node (ref "C18") (pin "1") (pinfunction "1_1") (pintype "passive"))
      (node (ref "C20") (pin "1") (pinfunction "1_1") (pintype "passive"))
      (node (ref "C25") (pin "1") (pinfunction "1_1") (pintype "passive"))
      (node (ref "C30") (pin "1") (pinfunction "1_1") (pintype "passive"))
      (node (ref "C33") (pin "1") (pinfunction "1_1") (pintype "passive"))
      (node (ref "C35") (pin "1") (pinfunction "1_1") (pintype "passive"))
      (node (ref "C36") (pin "1") (pinfunction "1_1") (pintype "passive"))
      (node (ref "C9") (pin "1") (pinfunction "1_1") (pintype "passive"))
      (node (ref "F1") (pin "2") (pinfunction "2_2") (pintype "passive"))
      (node (ref "IC10") (pin "5") (pinfunction "VCC_5") (pintype "power_in"))
      (node (ref "IC12") (pin "1") (pinfunction "AVDD_1") (pintype "bidirectional"))
      (node (ref "IC13") (pin "1") (pinfunction "AVDD_1") (pintype "bidirectional"))
      (node (ref "IC14") (pin "1") (pinfunction "AVDD_1") (pintype "bidirectional"))
      (node (ref "IC15") (pin "1") (pinfunction "AVDD_1") (pintype "bidirectional"))
      (node (ref "IC16") (pin "1") (pinfunction "AVDD_1") (pintype "bidirectional"))
      (node (ref "IC17") (pin "1") (pinfunction "AVDD_1") (pintype "bidirectional"))
      (node (ref "IC18") (pin "5") (pinfunction "VCC_5") (pintype "power_in"))
      (node (ref "IC19") (pin "5") (pinfunction "VCC_5") (pintype "power_in"))
      (node (ref "IC3") (pin "4") (pinfunction "VCCIO_4") (pintype "power_in"))
      (node (ref "IC5") (pin "5") (pinfunction "OUT_5") (pintype "bidirectional"))
      (node (ref "LED1") (pin "A1") (pinfunction "A_A1") (pintype "passive"))
      (node (ref "LED1") (pin "A2") (pinfunction "A_A2") (pintype "passive"))
      (node (ref "LED2") (pin "A1") (pinfunction "A_A1") (pintype "passive"))
      (node (ref "LED2") (pin "A2") (pinfunction "A_A2") (pintype "passive"))
      (node (ref "LED3") (pin "A1") (pinfunction "A_A1") (pintype "passive"))
      (node (ref "LED3") (pin "A2") (pinfunction "A_A2") (pintype "passive"))
      (node (ref "LED4") (pin "A1") (pinfunction "A_A1") (pintype "passive"))
      (node (ref "LED4") (pin "A2") (pinfunction "A_A2") (pintype "passive"))
      (node (ref "LED5") (pin "A1") (pinfunction "A_A1") (pintype "passive"))
      (node (ref "LED5") (pin "A2") (pinfunction "A_A2") (pintype "passive"))
      (node (ref "R18") (pin "1") (pinfunction "1_1") (pintype "passive"))
      (node (ref "R55") (pin "2") (pinfunction "2_2") (pintype "passive"))
    )
    (net (code "2") (name "+3V3_u") (class "Default")
      (node (ref "C22") (pin "1") (pinfunction "1_1") (pintype "passive"))
      (node (ref "C27") (pin "1") (pinfunction "1_1") (pintype "passive"))
      (node (ref "C28") (pin "1") (pinfunction "1_1") (pintype "passive"))
      (node (ref "C29") (pin "1") (pinfunction "1_1") (pintype "passive"))
      (node (ref "C32") (pin "1") (pinfunction "1_1") (pintype "passive"))
      (node (ref "F1") (pin "1") (pinfunction "1_1") (pintype "passive"))
      (node (ref "IC6") (pin "19") (pinfunction "VCC_19") (pintype "power_in"))
      (node (ref "IC6") (pin "31") (pinfunction "VCC_31") (pintype "power_in"))
      (node (ref "IC6") (pin "39") (pinfunction "AVCC_39") (pintype "power_in"))
      (node (ref "IC6") (pin "9") (pinfunction "VCC_9") (pintype "power_in"))
      (node (ref "OSC1") (pin "P$4") (pinfunction "VDD_P$4") (pintype "passive"))
      (node (ref "PDI") (pin "2") (pinfunction "2_2") (pintype "passive"))
      (node (ref "R48") (pin "2") (pinfunction "2_2") (pintype "passive"))
      (node (ref "R50") (pin "2") (pinfunction "2_2") (pintype "passive"))
    )
    (net (code "3") (name "+5V") (class "Default")
      (node (ref "+5V_TP") (pin "TP") (pinfunction "TP_TP") (pintype "input"))
      (node (ref "C10") (pin "1") (pinfunction "1_1") (pintype "passive"))
      (node (ref "C23") (pin "1") (pinfunction "1_1") (pintype "passive"))
      (node (ref "C31") (pin "1") (pinfunction "1_1") (pintype "passive"))
      (node (ref "C34") (pin "1") (pinfunction "1_1") (pintype "passive"))
      (node (ref "C37") (pin "1") (pinfunction "1_1") (pintype "passive"))
      (node (ref "C38") (pin "1") (pinfunction "1_1") (pintype "passive"))
      (node (ref "IC11") (pin "1") (pinfunction "IN_1") (pintype "bidirectional"))
      (node (ref "IC11") (pin "3") (pinfunction "EN_3") (pintype "bidirectional"))
      (node (ref "IC4") (pin "1") (pinfunction "VO_1") (pintype "bidirectional"))
      (node (ref "IC5") (pin "1") (pinfunction "IN_1") (pintype "bidirectional"))
      (node (ref "IC5") (pin "3") (pinfunction "EN_3") (pintype "bidirectional"))
      (node (ref "IC7") (pin "1") (pinfunction "OE_1") (pintype "input"))
      (node (ref "IC7") (pin "5") (pinfunction "VCC_5") (pintype "power_in"))
      (node (ref "IC8") (pin "1") (pinfunction "OE_1") (pintype "input"))
      (node (ref "IC8") (pin "5") (pinfunction "VCC_5") (pintype "power_in"))
      (node (ref "IC9") (pin "1") (pinfunction "OE_1") (pintype "input"))
      (node (ref "IC9") (pin "5") (pinfunction "VCC_5") (pintype "power_in"))
      (node (ref "SV1") (pin "10") (pinfunction "10_10") (pintype "passive"))
    )
    (net (code "4") (name "/+5_USB") (class "Default")
      (node (ref "C39") (pin "+") (pinfunction "+_+") (pintype "passive"))
      (node (ref "C5") (pin "1") (pinfunction "1_1") (pintype "passive"))
      (node (ref "C8") (pin "1") (pinfunction "1_1") (pintype "passive"))
      (node (ref "IC3") (pin "20") (pinfunction "VCC_20") (pintype "power_in"))
      (node (ref "IC4") (pin "8") (pinfunction "VP_8") (pintype "bidirectional"))
      (node (ref "L1") (pin "1") (pinfunction "1_1") (pintype "passive"))
      (node (ref "Q5") (pin "1") (pinfunction "S_1") (pintype "passive"))
      (node (ref "R17") (pin "2") (pinfunction "2_2") (pintype "passive"))
    )
    (net (code "5") (name "/5VUSB_INPUT") (class "Default")
      (node (ref "C3") (pin "1") (pinfunction "1_1") (pintype "passive"))
      (node (ref "IC2") (pin "P$5") (pinfunction "VBUS_P$5") (pintype "bidirectional"))
      (node (ref "L1") (pin "2") (pinfunction "2_2") (pintype "passive"))
      (node (ref "USB") (pin "P$1") (pinfunction "1_P$1") (pintype "bidirectional"))
    )
    (net (code "6") (name "/BAT_READ") (class "Default")
      (node (ref "IC6") (pin "41") (pinfunction "PA1/ADC1_41") (pintype "bidirectional"))
      (node (ref "R6") (pin "1") (pinfunction "1_1") (pintype "passive"))
    )
    (net (code "7") (name "/BAT_VOLTAGE") (class "Default")
      (node (ref "IC6") (pin "40") (pinfunction "PA0/ADC0/AREF_40") (pintype "bidirectional"))
      (node (ref "R4") (pin "2") (pinfunction "2_2") (pintype "passive"))
      (node (ref "R5") (pin "1") (pinfunction "1_1") (pintype "passive"))
    )
    (net (code "8") (name "/BLIGHT_EN") (class "Default")
      (node (ref "R12") (pin "1") (pinfunction "1_1") (pintype "passive"))
      (node (ref "SV1") (pin "1") (pinfunction "1_1") (pintype "passive"))
    )
    (net (code "9") (name "/BLIGHT_EN_UC") (class "Default")
      (node (ref "IC6") (pin "1") (pinfunction "PA5/ADC5_1") (pintype "bidirectional"))
      (node (ref "IC8") (pin "2") (pinfunction "I_2") (pintype "input"))
    )
    (net (code "10") (name "/BUTTON") (class "Default")
      (node (ref "C62") (pin "1") (pinfunction "1_1") (pintype "passive"))
      (node (ref "IC6") (pin "7") (pinfunction "PB3/ADC11/DAC1_7") (pintype "bidirectional"))
      (node (ref "R48") (pin "1") (pinfunction "1_1") (pintype "passive"))
      (node (ref "R9") (pin "2") (pinfunction "2_2") (pintype "passive"))
    )
    (net (code "11") (name "/CHARGE_ENABLE") (class "Default")
      (node (ref "IC6") (pin "5") (pinfunction "PB1/ADC9_5") (pintype "bidirectional"))
      (node (ref "Q4") (pin "2") (pinfunction "G_2") (pintype "passive"))
      (node (ref "R19") (pin "2") (pinfunction "2_2") (pintype "passive"))
    )
    (net (code "12") (name "/CLOCK_IN") (class "Default")
      (node (ref "CLKIN") (pin "4") (pinfunction "4_4") (pintype "passive"))
      (node (ref "IC18") (pin "2") (pinfunction "I_2") (pintype "input"))
      (node (ref "IC6") (pin "26") (pinfunction "~RXD1MISOPD6_26") (pintype "bidirectional"))
      (node (ref "R3") (pin "2") (pinfunction "2_2") (pintype "passive"))
    )
    (net (code "13") (name "/CLOCK_OUT") (class "Default")
      (node (ref "IC19") (pin "2") (pinfunction "I_2") (pintype "input"))
      (node (ref "IC6") (pin "27") (pinfunction "~~{TXD1SCKCLKOPD7}_27") (pintype "bidirectional"))
    )
    (net (code "14") (name "/CLOCK_OUT_ISO") (class "Default")
      (node (ref "IC12") (pin "2") (pinfunction "A1_IN_2") (pintype "bidirectional"))
      (node (ref "IC13") (pin "2") (pinfunction "A1_IN_2") (pintype "bidirectional"))
      (node (ref "IC14") (pin "2") (pinfunction "A1_IN_2") (pintype "bidirectional"))
      (node (ref "IC15") (pin "2") (pinfunction "A1_IN_2") (pintype "bidirectional"))
      (node (ref "IC16") (pin "2") (pinfunction "A1_IN_2") (pintype "bidirectional"))
      (node (ref "IC17") (pin "2") (pinfunction "A1_IN_2") (pintype "bidirectional"))
      (node (ref "IC18") (pin "4") (pinfunction "O_4") (pintype "tri_state"))
      (node (ref "IC19") (pin "4") (pinfunction "O_4") (pintype "tri_state"))
      (node (ref "IC7") (pin "2") (pinfunction "I_2") (pintype "input"))
    )
    (net (code "15") (name "/DEVICE_AT_0") (class "Default")
      (node (ref "IC12") (pin "3") (pinfunction "A2_OUT_3") (pintype "bidirectional"))
      (node (ref "IC6") (pin "16") (pinfunction "PC6/MISO/RXD1_16") (pintype "bidirectional"))
    )
    (net (code "16") (name "/DEVICE_AT_1") (class "Default")
      (node (ref "IC13") (pin "3") (pinfunction "A2_OUT_3") (pintype "bidirectional"))
      (node (ref "IC6") (pin "17") (pinfunction "PC7/SCK/TXD1/CLKO/EVO_17") (pintype "bidirectional"))
    )
    (net (code "17") (name "/DEVICE_AT_2") (class "Default")
      (node (ref "IC14") (pin "3") (pinfunction "A2_OUT_3") (pintype "bidirectional"))
      (node (ref "IC6") (pin "44") (pinfunction "PA4/ADC4_44") (pintype "bidirectional"))
    )
    (net (code "18") (name "/DEVICE_AT_3") (class "Default")
      (node (ref "IC15") (pin "3") (pinfunction "A2_OUT_3") (pintype "bidirectional"))
      (node (ref "IC6") (pin "36") (pinfunction "PR0/XTAL2_36") (pintype "bidirectional"))
    )
    (net (code "19") (name "/DEVICE_AT_4") (class "Default")
      (node (ref "IC16") (pin "3") (pinfunction "A2_OUT_3") (pintype "bidirectional"))
      (node (ref "IC6") (pin "42") (pinfunction "PA2/ADC2_42") (pintype "bidirectional"))
    )
    (net (code "20") (name "/DEVICE_AT_5") (class "Default")
      (node (ref "IC17") (pin "3") (pinfunction "A2_OUT_3") (pintype "bidirectional"))
      (node (ref "IC6") (pin "43") (pinfunction "PA3/ADC3_43") (pintype "bidirectional"))
    )
    (net (code "21") (name "/DISCHARGE_BAT") (class "Default")
      (node (ref "IC6") (pin "6") (pinfunction "PB2/ADC10/DAC0_6") (pintype "bidirectional"))
      (node (ref "R14") (pin "1") (pinfunction "1_1") (pintype "passive"))
    )
    (net (code "22") (name "/EN_CLOCK_IN") (class "Default")
      (node (ref "IC18") (pin "1") (pinfunction "OE_1") (pintype "input"))
      (node (ref "IC6") (pin "22") (pinfunction "~OC0CRXD0PD2_22") (pintype "bidirectional"))
      (node (ref "R54") (pin "1") (pinfunction "1_1") (pintype "passive"))
    )
    (net (code "23") (name "/EN_CLOCK_OUT") (class "Default")
      (node (ref "IC19") (pin "1") (pinfunction "OE_1") (pintype "input"))
      (node (ref "IC6") (pin "21") (pinfunction "~OC0BXCK0PD1_21") (pintype "bidirectional"))
      (node (ref "R55") (pin "1") (pinfunction "1_1") (pintype "passive"))
    )
    (net (code "24") (name "/FTDI_CTS") (class "Default")
      (node (ref "IC3") (pin "11") (pinfunction "~{CTS}_11") (pintype "input"))
      (node (ref "IC6") (pin "29") (pinfunction "~XCK0OC0BSCLPE1_29") (pintype "bidirectional"))
    )
    (net (code "25") (name "/FTDI_RTS") (class "Default")
      (node (ref "IC3") (pin "3") (pinfunction "~{RTS}_3") (pintype "output"))
      (node (ref "IC6") (pin "28") (pinfunction "~{OC0ASDAPE0}_28") (pintype "bidirectional"))
    )
    (net (code "26") (name "/FTDI_RXD") (class "Default")
      (node (ref "IC3") (pin "5") (pinfunction "RXD_5") (pintype "input"))
      (node (ref "IC6") (pin "33") (pinfunction "~TXD0OC0DPE3_33") (pintype "bidirectional"))
    )
    (net (code "27") (name "/FTDI_TXD") (class "Default")
      (node (ref "IC3") (pin "1") (pinfunction "TXD_1") (pintype "output"))
      (node (ref "IC6") (pin "32") (pinfunction "~RXD0OC0CPE2_32") (pintype "bidirectional"))
    )
    (net (code "28") (name "/IDC_CLOCK_OUT") (class "Default")
      (node (ref "R11") (pin "1") (pinfunction "1_1") (pintype "passive"))
      (node (ref "SV1") (pin "2") (pinfunction "2_2") (pintype "passive"))
    )
    (net (code "29") (name "/LED_CLK_0") (class "Default")
      (node (ref "IC6") (pin "10") (pinfunction "PC0/OC0A/SDA_10") (pintype "bidirectional"))
      (node (ref "R21") (pin "1") (pinfunction "1_1") (pintype "passive"))
    )
    (net (code "30") (name "/LED_CLK_1") (class "Default")
      (node (ref "IC6") (pin "3") (pinfunction "PA7/ADC7/AC0-OUT_3") (pintype "bidirectional"))
      (node (ref "R22") (pin "1") (pinfunction "1_1") (pintype "passive"))
    )
    (net (code "31") (name "/LED_CLK_2") (class "Default")
      (node (ref "IC6") (pin "14") (pinfunction "PC4/OC1A/#SS_14") (pintype "bidirectional"))
      (node (ref "R23") (pin "1") (pinfunction "1_1") (pintype "passive"))
    )
    (net (code "32") (name "/LED_CLK_3") (class "Default")
      (node (ref "IC6") (pin "11") (pinfunction "PC1/OC0B/XCK0/SCL_11") (pintype "bidirectional"))
      (node (ref "R27") (pin "1") (pinfunction "1_1") (pintype "passive"))
    )
    (net (code "33") (name "/LED_CLK_4") (class "Default")
      (node (ref "IC6") (pin "2") (pinfunction "PA6/ADC6_2") (pintype "bidirectional"))
      (node (ref "R28") (pin "1") (pinfunction "1_1") (pintype "passive"))
    )
    (net (code "34") (name "/LED_CLK_5") (class "Default")
      (node (ref "IC6") (pin "15") (pinfunction "PC5/OC1B/MOSI/XCK1_15") (pintype "bidirectional"))
      (node (ref "R29") (pin "1") (pinfunction "1_1") (pintype "passive"))
    )
    (net (code "35") (name "/LED_LOCK") (class "Default")
      (node (ref "IC6") (pin "24") (pinfunction "~{#SSPD4}_24") (pintype "bidirectional"))
      (node (ref "R24") (pin "1") (pinfunction "1_1") (pintype "passive"))
    )
    (net (code "36") (name "/LED_PWR") (class "Default")
      (node (ref "IC6") (pin "20") (pinfunction "~{OC0APD0}_20") (pintype "bidirectional"))
      (node (ref "R25") (pin "1") (pinfunction "1_1") (pintype "passive"))
    )
    (net (code "37") (name "/LED_REP") (class "Default")
      (node (ref "IC6") (pin "23") (pinfunction "~OC0DTXD0PD3_23") (pintype "bidirectional"))
      (node (ref "R30") (pin "1") (pinfunction "1_1") (pintype "passive"))
    )
    (net (code "38") (name "/PDI-CLK") (class "Default")
      (node (ref "C40") (pin "1") (pinfunction "1_1") (pintype "passive"))
      (node (ref "IC6") (pin "35") (pinfunction "RESET/PDI-CLK_35") (pintype "input"))
      (node (ref "PDI") (pin "5") (pinfunction "5_5") (pintype "passive"))
      (node (ref "R50") (pin "1") (pinfunction "1_1") (pintype "passive"))
    )
    (net (code "39") (name "/PDI-DATA") (class "Default")
      (node (ref "IC6") (pin "34") (pinfunction "PDI-DATA_34") (pintype "bidirectional"))
      (node (ref "PDI") (pin "1") (pinfunction "1_1") (pintype "passive"))
    )
    (net (code "40") (name "/PWR_GOOD") (class "Default")
      (node (ref "IC4") (pin "6") (pinfunction "P_BAR_6") (pintype "bidirectional"))
      (node (ref "IC6") (pin "4") (pinfunction "PB0/ADC8/AREF_4") (pintype "bidirectional"))
    )
    (net (code "41") (name "/RX") (class "Default")
      (node (ref "IC10") (pin "2") (pinfunction "I_2") (pintype "input"))
      (node (ref "R16") (pin "1") (pinfunction "1_1") (pintype "passive"))
      (node (ref "SV1") (pin "6") (pinfunction "6_6") (pintype "passive"))
    )
    (net (code "42") (name "/STATE") (class "Default")
      (node (ref "IC6") (pin "25") (pinfunction "~XCK1MOSIPD5_25") (pintype "bidirectional"))
      (node (ref "R31") (pin "1") (pinfunction "1_1") (pintype "passive"))
    )
    (net (code "43") (name "/TX") (class "Default")
      (node (ref "R10") (pin "1") (pinfunction "1_1") (pintype "passive"))
      (node (ref "SV1") (pin "4") (pinfunction "4_4") (pintype "passive"))
    )
    (net (code "44") (name "/UC_RX") (class "Default")
      (node (ref "IC10") (pin "4") (pinfunction "O_4") (pintype "tri_state"))
      (node (ref "IC6") (pin "12") (pinfunction "PC2/OC0C/RXD0_12") (pintype "bidirectional"))
    )
    (net (code "45") (name "/UC_TX") (class "Default")
      (node (ref "IC6") (pin "13") (pinfunction "PC3/OC0D/TXD0_13") (pintype "bidirectional"))
      (node (ref "IC9") (pin "2") (pinfunction "I_2") (pintype "input"))
    )
    (net (code "46") (name "/V_BATT") (class "Default")
      (node (ref "BATEN") (pin "1") (pinfunction "1_1") (pintype "passive"))
      (node (ref "IC1") (pin "3") (pinfunction "VBAT_3") (pintype "bidirectional"))
      (node (ref "IC4") (pin "2") (pinfunction "VS_2") (pintype "bidirectional"))
      (node (ref "Q1") (pin "1") (pinfunction "S_1") (pintype "passive"))
      (node (ref "R15") (pin "1") (pinfunction "1_1") (pintype "passive"))
      (node (ref "R7") (pin "1") (pinfunction "1_1") (pintype "passive"))
    )
    (net (code "47") (name "GND") (class "Default")
      (node (ref "BUTTON") (pin "1") (pinfunction "3_1") (pintype "passive"))
      (node (ref "C1") (pin "2") (pinfunction "2_2") (pintype "passive"))
      (node (ref "C10") (pin "2") (pinfunction "2_2") (pintype "passive"))
      (node (ref "C11") (pin "2") (pinfunction "2_2") (pintype "passive"))
      (node (ref "C12") (pin "2") (pinfunction "2_2") (pintype "passive"))
      (node (ref "C14") (pin "2") (pinfunction "2_2") (pintype "passive"))
      (node (ref "C16") (pin "2") (pinfunction "2_2") (pintype "passive"))
      (node (ref "C18") (pin "2") (pinfunction "2_2") (pintype "passive"))
      (node (ref "C2") (pin "2") (pinfunction "2_2") (pintype "passive"))
      (node (ref "C20") (pin "2") (pinfunction "2_2") (pintype "passive"))
      (node (ref "C22") (pin "2") (pinfunction "2_2") (pintype "passive"))
      (node (ref "C23") (pin "2") (pinfunction "2_2") (pintype "passive"))
      (node (ref "C24") (pin "2") (pinfunction "2_2") (pintype "passive"))
      (node (ref "C25") (pin "2") (pinfunction "2_2") (pintype "passive"))
      (node (ref "C27") (pin "2") (pinfunction "2_2") (pintype "passive"))
      (node (ref "C28") (pin "2") (pinfunction "2_2") (pintype "passive"))
      (node (ref "C29") (pin "2") (pinfunction "2_2") (pintype "passive"))
      (node (ref "C3") (pin "2") (pinfunction "2_2") (pintype "passive"))
      (node (ref "C30") (pin "2") (pinfunction "2_2") (pintype "passive"))
      (node (ref "C31") (pin "2") (pinfunction "2_2") (pintype "passive"))
      (node (ref "C32") (pin "2") (pinfunction "2_2") (pintype "passive"))
      (node (ref "C33") (pin "2") (pinfunction "2_2") (pintype "passive"))
      (node (ref "C34") (pin "2") (pinfunction "2_2") (pintype "passive"))
      (node (ref "C35") (pin "2") (pinfunction "2_2") (pintype "passive"))
      (node (ref "C36") (pin "2") (pinfunction "2_2") (pintype "passive"))
      (node (ref "C37") (pin "2") (pinfunction "2_2") (pintype "passive"))
      (node (ref "C38") (pin "2") (pinfunction "2_2") (pintype "passive"))
      (node (ref "C39") (pin "-") (pinfunction "-_-") (pintype "passive"))
      (node (ref "C4") (pin "2") (pinfunction "2_2") (pintype "passive"))
      (node (ref "C40") (pin "2") (pinfunction "2_2") (pintype "passive"))
      (node (ref "C5") (pin "2") (pinfunction "2_2") (pintype "passive"))
      (node (ref "C6") (pin "2") (pinfunction "2_2") (pintype "passive"))
      (node (ref "C62") (pin "2") (pinfunction "2_2") (pintype "passive"))
      (node (ref "C7") (pin "2") (pinfunction "2_2") (pintype "passive"))
      (node (ref "C8") (pin "2") (pinfunction "2_2") (pintype "passive"))
      (node (ref "C9") (pin "2") (pinfunction "2_2") (pintype "passive"))
      (node (ref "CLKIN") (pin "5") (pinfunction "5_5") (pintype "passive"))
      (node (ref "GND_TP0") (pin "TP") (pinfunction "TP_TP") (pintype "input"))
      (node (ref "GND_TP1") (pin "TP") (pinfunction "TP_TP") (pintype "input"))
      (node (ref "IC1") (pin "2") (pinfunction "VSS_2") (pintype "bidirectional"))
      (node (ref "IC10") (pin "1") (pinfunction "OE_1") (pintype "input"))
      (node (ref "IC10") (pin "3") (pinfunction "GND_3") (pintype "power_in"))
      (node (ref "IC11") (pin "2") (pinfunction "GND_2") (pintype "bidirectional"))
      (node (ref "IC12") (pin "4") (pinfunction "AGND_4") (pintype "bidirectional"))
      (node (ref "IC13") (pin "4") (pinfunction "AGND_4") (pintype "bidirectional"))
      (node (ref "IC14") (pin "4") (pinfunction "AGND_4") (pintype "bidirectional"))
      (node (ref "IC15") (pin "4") (pinfunction "AGND_4") (pintype "bidirectional"))
      (node (ref "IC16") (pin "4") (pinfunction "AGND_4") (pintype "bidirectional"))
      (node (ref "IC17") (pin "4") (pinfunction "AGND_4") (pintype "bidirectional"))
      (node (ref "IC18") (pin "3") (pinfunction "GND_3") (pintype "power_in"))
      (node (ref "IC19") (pin "3") (pinfunction "GND_3") (pintype "power_in"))
      (node (ref "IC2") (pin "P$2") (pinfunction "GND_P$2") (pintype "bidirectional"))
      (node (ref "IC3") (pin "18") (pinfunction "GND_18") (pintype "power_in"))
      (node (ref "IC3") (pin "21") (pinfunction "GND_21") (pintype "power_in"))
      (node (ref "IC3") (pin "25") (pinfunction "GND_25") (pintype "power_in"))
      (node (ref "IC3") (pin "26") (pinfunction "TEST_26") (pintype "input"))
      (node (ref "IC3") (pin "7") (pinfunction "GND_7") (pintype "power_in"))
      (node (ref "IC4") (pin "4") (pinfunction "GND_4") (pintype "bidirectional"))
      (node (ref "IC5") (pin "2") (pinfunction "GND_2") (pintype "bidirectional"))
      (node (ref "IC6") (pin "18") (pinfunction "GND_18") (pintype "power_in"))
      (node (ref "IC6") (pin "30") (pinfunction "GND_30") (pintype "power_in"))
      (node (ref "IC6") (pin "38") (pinfunction "GND_38") (pintype "power_in"))
      (node (ref "IC6") (pin "8") (pinfunction "GND_8") (pintype "power_in"))
      (node (ref "IC7") (pin "3") (pinfunction "GND_3") (pintype "power_in"))
      (node (ref "IC8") (pin "3") (pinfunction "GND_3") (pintype "power_in"))
      (node (ref "IC9") (pin "3") (pinfunction "GND_3") (pintype "power_in"))
      (node (ref "OSC1") (pin "P$2") (pinfunction "GND_P$2") (pintype "passive"))
      (node (ref "PDI") (pin "6") (pinfunction "6_6") (pintype "passive"))
      (node (ref "Q2") (pin "E") (pinfunction "E_E") (pintype "passive"))
      (node (ref "Q3") (pin "E") (pinfunction "E_E") (pintype "passive"))
      (node (ref "Q4") (pin "1") (pinfunction "S_1") (pintype "passive"))
      (node (ref "R1") (pin "2") (pinfunction "2_2") (pintype "passive"))
      (node (ref "R13") (pin "1") (pinfunction "1_1") (pintype "passive"))
      (node (ref "R16") (pin "2") (pinfunction "2_2") (pintype "passive"))
      (node (ref "R19") (pin "1") (pinfunction "1_1") (pintype "passive"))
      (node (ref "R5") (pin "2") (pinfunction "2_2") (pintype "passive"))
      (node (ref "R54") (pin "2") (pinfunction "2_2") (pintype "passive"))
      (node (ref "SV1") (pin "9") (pinfunction "9_9") (pintype "passive"))
      (node (ref "T1") (pin "2") (pinfunction "E_2") (pintype "passive"))
      (node (ref "T10") (pin "2") (pinfunction "E_2") (pintype "passive"))
      (node (ref "T2") (pin "2") (pinfunction "E_2") (pintype "passive"))
      (node (ref "T3") (pin "2") (pinfunction "E_2") (pintype "passive"))
      (node (ref "T4") (pin "2") (pinfunction "E_2") (pintype "passive"))
      (node (ref "T5") (pin "2") (pinfunction "E_2") (pintype "passive"))
      (node (ref "T6") (pin "2") (pinfunction "E_2") (pintype "passive"))
      (node (ref "T7") (pin "2") (pinfunction "E_2") (pintype "passive"))
      (node (ref "T8") (pin "2") (pinfunction "E_2") (pintype "passive"))
      (node (ref "T9") (pin "2") (pinfunction "E_2") (pintype "passive"))
      (node (ref "USB") (pin "P$5") (pinfunction "5_P$5") (pintype "bidirectional"))
      (node (ref "X1") (pin "2") (pinfunction "S_2") (pintype "passive"))
    )
    (net (code "48") (name "Net-(BUTTON-Pad2)") (class "Default")
      (node (ref "BUTTON") (pin "2") (pinfunction "2_2") (pintype "passive"))
      (node (ref "R9") (pin "1") (pinfunction "1_1") (pintype "passive"))
    )
    (net (code "49") (name "Net-(CLKIN-Pad1)") (class "Default")
      (node (ref "CLKIN") (pin "1") (pinfunction "1_1") (pintype "passive"))
      (node (ref "R2") (pin "2") (pinfunction "2_2") (pintype "passive"))
      (node (ref "R3") (pin "1") (pinfunction "1_1") (pintype "passive"))
    )
    (net (code "50") (name "Net-(IC1-PROG)") (class "Default")
      (node (ref "IC1") (pin "5") (pinfunction "PROG_5") (pintype "bidirectional"))
      (node (ref "R13") (pin "2") (pinfunction "2_2") (pintype "passive"))
    )
    (net (code "51") (name "Net-(IC1-VDD)") (class "Default")
      (node (ref "IC1") (pin "4") (pinfunction "VDD_4") (pintype "bidirectional"))
      (node (ref "Q5") (pin "3") (pinfunction "D_3") (pintype "passive"))
    )
    (net (code "52") (name "Net-(IC3-3V3OUT)") (class "Default")
      (node (ref "C7") (pin "1") (pinfunction "1_1") (pintype "passive"))
      (node (ref "IC3") (pin "17") (pinfunction "3V3OUT_17") (pintype "output"))
    )
    (net (code "53") (name "Net-(IC3-USBDM)") (class "Default")
      (node (ref "C6") (pin "1") (pinfunction "1_1") (pintype "passive"))
      (node (ref "IC2") (pin "P$6") (pinfunction "IO1_P$6") (pintype "bidirectional"))
      (node (ref "IC3") (pin "16") (pinfunction "USBDM_16") (pintype "bidirectional"))
    )
    (net (code "54") (name "Net-(IC3-USBDP)") (class "Default")
      (node (ref "C4") (pin "1") (pinfunction "1_1") (pintype "passive"))
      (node (ref "IC2") (pin "P$4") (pinfunction "IO2_P$4") (pintype "bidirectional"))
      (node (ref "IC3") (pin "15") (pinfunction "USBDP_15") (pintype "bidirectional"))
    )
    (net (code "55") (name "Net-(IC3-~{RESET})") (class "Default")
      (node (ref "IC3") (pin "19") (pinfunction "~{RESET}_19") (pintype "input"))
      (node (ref "R18") (pin "2") (pinfunction "2_2") (pintype "passive"))
    )
    (net (code "56") (name "Net-(IC6-PR1{slash}XTAL1)") (class "Default")
      (node (ref "IC6") (pin "37") (pinfunction "PR1/XTAL1_37") (pintype "bidirectional"))
      (node (ref "OSC1") (pin "P$3") (pinfunction "OUTPUT_P$3") (pintype "passive"))
    )
    (net (code "57") (name "Net-(IC7A-O)") (class "Default")
      (node (ref "IC7") (pin "4") (pinfunction "O_4") (pintype "output"))
      (node (ref "R11") (pin "2") (pinfunction "2_2") (pintype "passive"))
    )
    (net (code "58") (name "Net-(IC8A-O)") (class "Default")
      (node (ref "IC8") (pin "4") (pinfunction "O_4") (pintype "output"))
      (node (ref "R12") (pin "2") (pinfunction "2_2") (pintype "passive"))
    )
    (net (code "59") (name "Net-(IC9A-O)") (class "Default")
      (node (ref "IC9") (pin "4") (pinfunction "O_4") (pintype "output"))
      (node (ref "R10") (pin "2") (pinfunction "2_2") (pintype "passive"))
    )
    (net (code "60") (name "Net-(IC11-OUT)") (class "Default")
      (node (ref "C24") (pin "1") (pinfunction "1_1") (pintype "passive"))
      (node (ref "IC11") (pin "5") (pinfunction "OUT_5") (pintype "bidirectional"))
      (node (ref "R2") (pin "1") (pinfunction "1_1") (pintype "passive"))
    )
    (net (code "61") (name "Net-(IC12-B1_OUT)") (class "Default")
      (node (ref "CLKOUT0") (pin "4") (pinfunction "4_4") (pintype "passive"))
      (node (ref "IC12") (pin "7") (pinfunction "B1_OUT_7") (pintype "bidirectional"))
    )
    (net (code "62") (name "Net-(IC12-B2_IN)") (class "Default")
      (node (ref "C26") (pin "1") (pinfunction "1_1") (pintype "passive"))
      (node (ref "CLKOUT0") (pin "1") (pinfunction "1_1") (pintype "passive"))
      (node (ref "IC12") (pin "6") (pinfunction "B2_IN_6") (pintype "bidirectional"))
      (node (ref "IC12") (pin "8") (pinfunction "BVDD_8") (pintype "bidirectional"))
    )
    (net (code "63") (name "Net-(IC12-BGND)") (class "Default")
      (node (ref "C26") (pin "2") (pinfunction "2_2") (pintype "passive"))
      (node (ref "CLKOUT0") (pin "5") (pinfunction "5_5") (pintype "passive"))
      (node (ref "IC12") (pin "5") (pinfunction "BGND_5") (pintype "bidirectional"))
    )
    (net (code "64") (name "Net-(IC13-B1_OUT)") (class "Default")
      (node (ref "CLKOUT1") (pin "4") (pinfunction "4_4") (pintype "passive"))
      (node (ref "IC13") (pin "7") (pinfunction "B1_OUT_7") (pintype "bidirectional"))
    )
    (net (code "65") (name "Net-(IC13-B2_IN)") (class "Default")
      (node (ref "C13") (pin "1") (pinfunction "1_1") (pintype "passive"))
      (node (ref "CLKOUT1") (pin "1") (pinfunction "1_1") (pintype "passive"))
      (node (ref "IC13") (pin "6") (pinfunction "B2_IN_6") (pintype "bidirectional"))
      (node (ref "IC13") (pin "8") (pinfunction "BVDD_8") (pintype "bidirectional"))
    )
    (net (code "66") (name "Net-(IC13-BGND)") (class "Default")
      (node (ref "C13") (pin "2") (pinfunction "2_2") (pintype "passive"))
      (node (ref "CLKOUT1") (pin "5") (pinfunction "5_5") (pintype "passive"))
      (node (ref "IC13") (pin "5") (pinfunction "BGND_5") (pintype "bidirectional"))
    )
    (net (code "67") (name "Net-(IC14-B1_OUT)") (class "Default")
      (node (ref "CLKOUT2") (pin "4") (pinfunction "4_4") (pintype "passive"))
      (node (ref "IC14") (pin "7") (pinfunction "B1_OUT_7") (pintype "bidirectional"))
    )
    (net (code "68") (name "Net-(IC14-B2_IN)") (class "Default")
      (node (ref "C15") (pin "1") (pinfunction "1_1") (pintype "passive"))
      (node (ref "CLKOUT2") (pin "1") (pinfunction "1_1") (pintype "passive"))
      (node (ref "IC14") (pin "6") (pinfunction "B2_IN_6") (pintype "bidirectional"))
      (node (ref "IC14") (pin "8") (pinfunction "BVDD_8") (pintype "bidirectional"))
    )
    (net (code "69") (name "Net-(IC14-BGND)") (class "Default")
      (node (ref "C15") (pin "2") (pinfunction "2_2") (pintype "passive"))
      (node (ref "CLKOUT2") (pin "5") (pinfunction "5_5") (pintype "passive"))
      (node (ref "IC14") (pin "5") (pinfunction "BGND_5") (pintype "bidirectional"))
    )
    (net (code "70") (name "Net-(IC15-B1_OUT)") (class "Default")
      (node (ref "CLKOUT3") (pin "4") (pinfunction "4_4") (pintype "passive"))
      (node (ref "IC15") (pin "7") (pinfunction "B1_OUT_7") (pintype "bidirectional"))
    )
    (net (code "71") (name "Net-(IC15-B2_IN)") (class "Default")
      (node (ref "C17") (pin "1") (pinfunction "1_1") (pintype "passive"))
      (node (ref "CLKOUT3") (pin "1") (pinfunction "1_1") (pintype "passive"))
      (node (ref "IC15") (pin "6") (pinfunction "B2_IN_6") (pintype "bidirectional"))
      (node (ref "IC15") (pin "8") (pinfunction "BVDD_8") (pintype "bidirectional"))
    )
    (net (code "72") (name "Net-(IC15-BGND)") (class "Default")
      (node (ref "C17") (pin "2") (pinfunction "2_2") (pintype "passive"))
      (node (ref "CLKOUT3") (pin "5") (pinfunction "5_5") (pintype "passive"))
      (node (ref "IC15") (pin "5") (pinfunction "BGND_5") (pintype "bidirectional"))
    )
    (net (code "73") (name "Net-(IC16-B1_OUT)") (class "Default")
      (node (ref "CLKOUT4") (pin "4") (pinfunction "4_4") (pintype "passive"))
      (node (ref "IC16") (pin "7") (pinfunction "B1_OUT_7") (pintype "bidirectional"))
    )
    (net (code "74") (name "Net-(IC16-B2_IN)") (class "Default")
      (node (ref "C19") (pin "1") (pinfunction "1_1") (pintype "passive"))
      (node (ref "CLKOUT4") (pin "1") (pinfunction "1_1") (pintype "passive"))
      (node (ref "IC16") (pin "6") (pinfunction "B2_IN_6") (pintype "bidirectional"))
      (node (ref "IC16") (pin "8") (pinfunction "BVDD_8") (pintype "bidirectional"))
    )
    (net (code "75") (name "Net-(IC16-BGND)") (class "Default")
      (node (ref "C19") (pin "2") (pinfunction "2_2") (pintype "passive"))
      (node (ref "CLKOUT4") (pin "5") (pinfunction "5_5") (pintype "passive"))
      (node (ref "IC16") (pin "5") (pinfunction "BGND_5") (pintype "bidirectional"))
    )
    (net (code "76") (name "Net-(IC17-B1_OUT)") (class "Default")
      (node (ref "CLKOUT5") (pin "4") (pinfunction "4_4") (pintype "passive"))
      (node (ref "IC17") (pin "7") (pinfunction "B1_OUT_7") (pintype "bidirectional"))
    )
    (net (code "77") (name "Net-(IC17-B2_IN)") (class "Default")
      (node (ref "C21") (pin "1") (pinfunction "1_1") (pintype "passive"))
      (node (ref "CLKOUT5") (pin "1") (pinfunction "1_1") (pintype "passive"))
      (node (ref "IC17") (pin "6") (pinfunction "B2_IN_6") (pintype "bidirectional"))
      (node (ref "IC17") (pin "8") (pinfunction "BVDD_8") (pintype "bidirectional"))
    )
    (net (code "78") (name "Net-(IC17-BGND)") (class "Default")
      (node (ref "C21") (pin "2") (pinfunction "2_2") (pintype "passive"))
      (node (ref "CLKOUT5") (pin "5") (pinfunction "5_5") (pintype "passive"))
      (node (ref "IC17") (pin "5") (pinfunction "BGND_5") (pintype "bidirectional"))
    )
    (net (code "79") (name "Net-(LED1A-C)") (class "Default")
      (node (ref "LED1") (pin "C1") (pinfunction "C_C1") (pintype "passive"))
      (node (ref "R40") (pin "1") (pinfunction "1_1") (pintype "passive"))
    )
    (net (code "80") (name "Net-(LED1B-C)") (class "Default")
      (node (ref "LED1") (pin "C2") (pinfunction "C_C2") (pintype "passive"))
      (node (ref "R33") (pin "1") (pinfunction "1_1") (pintype "passive"))
    )
    (net (code "81") (name "Net-(LED2A-C)") (class "Default")
      (node (ref "LED2") (pin "C1") (pinfunction "C_C1") (pintype "passive"))
      (node (ref "R41") (pin "1") (pinfunction "1_1") (pintype "passive"))
    )
    (net (code "82") (name "Net-(LED2B-C)") (class "Default")
      (node (ref "LED2") (pin "C2") (pinfunction "C_C2") (pintype "passive"))
      (node (ref "R34") (pin "1") (pinfunction "1_1") (pintype "passive"))
    )
    (net (code "83") (name "Net-(LED3A-C)") (class "Default")
      (node (ref "LED3") (pin "C1") (pinfunction "C_C1") (pintype "passive"))
      (node (ref "R42") (pin "1") (pinfunction "1_1") (pintype "passive"))
    )
    (net (code "84") (name "Net-(LED3B-C)") (class "Default")
      (node (ref "LED3") (pin "C2") (pinfunction "C_C2") (pintype "passive"))
      (node (ref "R35") (pin "1") (pinfunction "1_1") (pintype "passive"))
    )
    (net (code "85") (name "Net-(LED4A-C)") (class "Default")
      (node (ref "LED4") (pin "C1") (pinfunction "C_C1") (pintype "passive"))
      (node (ref "R44") (pin "1") (pinfunction "1_1") (pintype "passive"))
    )
    (net (code "86") (name "Net-(LED4B-C)") (class "Default")
      (node (ref "LED4") (pin "C2") (pinfunction "C_C2") (pintype "passive"))
      (node (ref "R36") (pin "1") (pinfunction "1_1") (pintype "passive"))
    )
    (net (code "87") (name "Net-(LED5A-C)") (class "Default")
      (node (ref "LED5") (pin "C1") (pinfunction "C_C1") (pintype "passive"))
      (node (ref "R45") (pin "1") (pinfunction "1_1") (pintype "passive"))
    )
    (net (code "88") (name "Net-(LED5B-C)") (class "Default")
      (node (ref "LED5") (pin "C2") (pinfunction "C_C2") (pintype "passive"))
      (node (ref "R37") (pin "1") (pinfunction "1_1") (pintype "passive"))
    )
    (net (code "89") (name "Net-(Q1-D)") (class "Default")
      (node (ref "Q1") (pin "3") (pinfunction "D_3") (pintype "passive"))
      (node (ref "R4") (pin "1") (pinfunction "1_1") (pintype "passive"))
    )
    (net (code "90") (name "Net-(Q1-G)") (class "Default")
      (node (ref "Q1") (pin "2") (pinfunction "G_2") (pintype "passive"))
      (node (ref "Q2") (pin "C") (pinfunction "C_C") (pintype "passive"))
      (node (ref "R7") (pin "2") (pinfunction "2_2") (pintype "passive"))
    )
    (net (code "91") (name "Net-(Q2-PadB)") (class "Default")
      (node (ref "Q2") (pin "B") (pinfunction "B_B") (pintype "passive"))
      (node (ref "R6") (pin "2") (pinfunction "2_2") (pintype "passive"))
    )
    (net (code "92") (name "Net-(Q3-PadB)") (class "Default")
      (node (ref "Q3") (pin "B") (pinfunction "B_B") (pintype "passive"))
      (node (ref "R14") (pin "2") (pinfunction "2_2") (pintype "passive"))
    )
    (net (code "93") (name "Net-(Q3-PadC)") (class "Default")
      (node (ref "Q3") (pin "C") (pinfunction "C_C") (pintype "passive"))
      (node (ref "R15") (pin "2") (pinfunction "2_2") (pintype "passive"))
    )
    (net (code "94") (name "Net-(Q4-D)") (class "Default")
      (node (ref "Q4") (pin "3") (pinfunction "D_3") (pintype "passive"))
      (node (ref "Q5") (pin "2") (pinfunction "G_2") (pintype "passive"))
      (node (ref "R17") (pin "1") (pinfunction "1_1") (pintype "passive"))
    )
    (net (code "95") (name "Net-(T1-B)") (class "Default")
      (node (ref "R21") (pin "2") (pinfunction "2_2") (pintype "passive"))
      (node (ref "T1") (pin "1") (pinfunction "B_1") (pintype "passive"))
    )
    (net (code "96") (name "Net-(T1-C)") (class "Default")
      (node (ref "R33") (pin "2") (pinfunction "2_2") (pintype "passive"))
      (node (ref "T1") (pin "3") (pinfunction "C_3") (pintype "passive"))
    )
    (net (code "97") (name "Net-(T2-B)") (class "Default")
      (node (ref "R27") (pin "2") (pinfunction "2_2") (pintype "passive"))
      (node (ref "T2") (pin "1") (pinfunction "B_1") (pintype "passive"))
    )
    (net (code "98") (name "Net-(T2-C)") (class "Default")
      (node (ref "R40") (pin "2") (pinfunction "2_2") (pintype "passive"))
      (node (ref "T2") (pin "3") (pinfunction "C_3") (pintype "passive"))
    )
    (net (code "99") (name "Net-(T3-B)") (class "Default")
      (node (ref "R22") (pin "2") (pinfunction "2_2") (pintype "passive"))
      (node (ref "T3") (pin "1") (pinfunction "B_1") (pintype "passive"))
    )
    (net (code "100") (name "Net-(T3-C)") (class "Default")
      (node (ref "R34") (pin "2") (pinfunction "2_2") (pintype "passive"))
      (node (ref "T3") (pin "3") (pinfunction "C_3") (pintype "passive"))
    )
    (net (code "101") (name "Net-(T4-B)") (class "Default")
      (node (ref "R28") (pin "2") (pinfunction "2_2") (pintype "passive"))
      (node (ref "T4") (pin "1") (pinfunction "B_1") (pintype "passive"))
    )
    (net (code "102") (name "Net-(T4-C)") (class "Default")
      (node (ref "R41") (pin "2") (pinfunction "2_2") (pintype "passive"))
      (node (ref "T4") (pin "3") (pinfunction "C_3") (pintype "passive"))
    )
    (net (code "103") (name "Net-(T5-B)") (class "Default")
      (node (ref "R23") (pin "2") (pinfunction "2_2") (pintype "passive"))
      (node (ref "T5") (pin "1") (pinfunction "B_1") (pintype "passive"))
    )
    (net (code "104") (name "Net-(T5-C)") (class "Default")
      (node (ref "R35") (pin "2") (pinfunction "2_2") (pintype "passive"))
      (node (ref "T5") (pin "3") (pinfunction "C_3") (pintype "passive"))
    )
    (net (code "105") (name "Net-(T6-B)") (class "Default")
      (node (ref "R29") (pin "2") (pinfunction "2_2") (pintype "passive"))
      (node (ref "T6") (pin "1") (pinfunction "B_1") (pintype "passive"))
    )
    (net (code "106") (name "Net-(T6-C)") (class "Default")
      (node (ref "R42") (pin "2") (pinfunction "2_2") (pintype "passive"))
      (node (ref "T6") (pin "3") (pinfunction "C_3") (pintype "passive"))
    )
    (net (code "107") (name "Net-(T7-B)") (class "Default")
      (node (ref "R24") (pin "2") (pinfunction "2_2") (pintype "passive"))
      (node (ref "T7") (pin "1") (pinfunction "B_1") (pintype "passive"))
    )
    (net (code "108") (name "Net-(T7-C)") (class "Default")
      (node (ref "R36") (pin "2") (pinfunction "2_2") (pintype "passive"))
      (node (ref "T7") (pin "3") (pinfunction "C_3") (pintype "passive"))
    )
    (net (code "109") (name "Net-(T8-B)") (class "Default")
      (node (ref "R30") (pin "2") (pinfunction "2_2") (pintype "passive"))
      (node (ref "T8") (pin "1") (pinfunction "B_1") (pintype "passive"))
    )
    (net (code "110") (name "Net-(T8-C)") (class "Default")
      (node (ref "R44") (pin "2") (pinfunction "2_2") (pintype "passive"))
      (node (ref "T8") (pin "3") (pinfunction "C_3") (pintype "passive"))
    )
    (net (code "111") (name "Net-(T9-B)") (class "Default")
      (node (ref "R25") (pin "2") (pinfunction "2_2") (pintype "passive"))
      (node (ref "T9") (pin "1") (pinfunction "B_1") (pintype "passive"))
    )
    (net (code "112") (name "Net-(T9-C)") (class "Default")
      (node (ref "R37") (pin "2") (pinfunction "2_2") (pintype "passive"))
      (node (ref "T9") (pin "3") (pinfunction "C_3") (pintype "passive"))
    )
    (net (code "113") (name "Net-(T10-B)") (class "Default")
      (node (ref "R31") (pin "2") (pinfunction "2_2") (pintype "passive"))
      (node (ref "T10") (pin "1") (pinfunction "B_1") (pintype "passive"))
    )
    (net (code "114") (name "Net-(T10-C)") (class "Default")
      (node (ref "R45") (pin "2") (pinfunction "2_2") (pintype "passive"))
      (node (ref "T10") (pin "3") (pinfunction "C_3") (pintype "passive"))
    )
    (net (code "115") (name "Net-(USB-2)") (class "Default")
      (node (ref "IC2") (pin "P$1") (pinfunction "IO1_P$1") (pintype "bidirectional"))
      (node (ref "USB") (pin "P$2") (pinfunction "2_P$2") (pintype "bidirectional"))
    )
    (net (code "116") (name "Net-(USB-3)") (class "Default")
      (node (ref "IC2") (pin "P$3") (pinfunction "IO2_P$3") (pintype "bidirectional"))
      (node (ref "USB") (pin "P$3") (pinfunction "3_P$3") (pintype "bidirectional"))
    )
    (net (code "117") (name "Net-(USB-P$1)") (class "Default")
      (node (ref "R1") (pin "1") (pinfunction "1_1") (pintype "passive"))
      (node (ref "USB") (pin "SHIELD_1") (pinfunction "P$1_SHIELD_1") (pintype "bidirectional"))
    )
    (net (code "118") (name "Net-(USB-P$4)") (class "Default")
      (node (ref "C2") (pin "1") (pinfunction "1_1") (pintype "passive"))
      (node (ref "USB") (pin "SHIELD_4") (pinfunction "P$4_SHIELD_4") (pintype "bidirectional"))
    )
    (net (code "119") (name "Net-(X1A-S)") (class "Default")
      (node (ref "BATEN") (pin "2") (pinfunction "2_2") (pintype "passive"))
      (node (ref "BAT_TP") (pin "TP") (pinfunction "TP_TP") (pintype "input"))
      (node (ref "X1") (pin "1") (pinfunction "S_1") (pintype "passive"))
    )
    (net (code "120") (name "unconnected-(BATEN-Pad3)") (class "Default")
      (node (ref "BATEN") (pin "3") (pinfunction "3_3") (pintype "passive"))
    )
    (net (code "121") (name "unconnected-(BUTTON-1-Pad3)") (class "Default")
      (node (ref "BUTTON") (pin "3") (pinfunction "1_3") (pintype "passive"))
    )
    (net (code "122") (name "unconnected-(IC1-STAT-Pad1)") (class "Default")
      (node (ref "IC1") (pin "1") (pinfunction "STAT_1") (pintype "bidirectional"))
    )
    (net (code "123") (name "unconnected-(IC3-CBUS0-Pad23)") (class "Default")
      (node (ref "IC3") (pin "23") (pinfunction "CBUS0_23") (pintype "bidirectional"))
    )
    (net (code "124") (name "unconnected-(IC3-CBUS1-Pad22)") (class "Default")
      (node (ref "IC3") (pin "22") (pinfunction "CBUS1_22") (pintype "bidirectional"))
    )
    (net (code "125") (name "unconnected-(IC3-CBUS2-Pad13)") (class "Default")
      (node (ref "IC3") (pin "13") (pinfunction "CBUS2_13") (pintype "bidirectional"))
    )
    (net (code "126") (name "unconnected-(IC3-CBUS3-Pad14)") (class "Default")
      (node (ref "IC3") (pin "14") (pinfunction "CBUS3_14") (pintype "bidirectional"))
    )
    (net (code "127") (name "unconnected-(IC3-CBUS4-Pad12)") (class "Default")
      (node (ref "IC3") (pin "12") (pinfunction "CBUS4_12") (pintype "bidirectional"))
    )
    (net (code "128") (name "unconnected-(IC3-OSCI-Pad27)") (class "Default")
      (node (ref "IC3") (pin "27") (pinfunction "OSCI_27") (pintype "input"))
    )
    (net (code "129") (name "unconnected-(IC3-OSCO-Pad28)") (class "Default")
      (node (ref "IC3") (pin "28") (pinfunction "OSCO_28") (pintype "output"))
    )
    (net (code "130") (name "unconnected-(IC3-~{DCD}-Pad10)") (class "Default")
      (node (ref "IC3") (pin "10") (pinfunction "~{DCD}_10") (pintype "input"))
    )
    (net (code "131") (name "unconnected-(IC3-~{DSR}-Pad9)") (class "Default")
      (node (ref "IC3") (pin "9") (pinfunction "~{DSR}_9") (pintype "input"))
    )
    (net (code "132") (name "unconnected-(IC3-~{DTR}-Pad2)") (class "Default")
      (node (ref "IC3") (pin "2") (pinfunction "~{DTR}_2") (pintype "output"))
    )
    (net (code "133") (name "unconnected-(IC3-~{RI}-Pad6)") (class "Default")
      (node (ref "IC3") (pin "6") (pinfunction "~{RI}_6") (pintype "input"))
    )
    (net (code "134") (name "unconnected-(IC4-NC5-Pad5)") (class "Default")
      (node (ref "IC4") (pin "5") (pinfunction "NC5_5") (pintype "bidirectional"))
    )
    (net (code "135") (name "unconnected-(IC4-NC7-Pad7)") (class "Default")
      (node (ref "IC4") (pin "7") (pinfunction "NC7_7") (pintype "bidirectional"))
    )
    (net (code "136") (name "unconnected-(IC4-S_BAR-Pad3)") (class "Default")
      (node (ref "IC4") (pin "3") (pinfunction "S_BAR_3") (pintype "bidirectional"))
    )
    (net (code "137") (name "unconnected-(IC5-N{slash}C-Pad4)") (class "Default")
      (node (ref "IC5") (pin "4") (pinfunction "N/C_4") (pintype "bidirectional"))
    )
    (net (code "138") (name "unconnected-(IC11-N{slash}C-Pad4)") (class "Default")
      (node (ref "IC11") (pin "4") (pinfunction "N/C_4") (pintype "bidirectional"))
    )
    (net (code "139") (name "unconnected-(OSC1-STANDBY#-PadP$1)") (class "Default")
      (node (ref "OSC1") (pin "P$1") (pinfunction "STANDBY#_P$1") (pintype "passive"))
    )
    (net (code "140") (name "unconnected-(PDI-Pad3)") (class "Default")
      (node (ref "PDI") (pin "3") (pinfunction "3_3") (pintype "passive"))
    )
    (net (code "141") (name "unconnected-(PDI-Pad4)") (class "Default")
      (node (ref "PDI") (pin "4") (pinfunction "4_4") (pintype "passive"))
    )
    (net (code "142") (name "unconnected-(SV1-Pad3)") (class "Default")
      (node (ref "SV1") (pin "3") (pinfunction "3_3") (pintype "passive"))
    )
    (net (code "143") (name "unconnected-(SV1-Pad5)") (class "Default")
      (node (ref "SV1") (pin "5") (pinfunction "5_5") (pintype "passive"))
    )
    (net (code "144") (name "unconnected-(SV1-Pad7)") (class "Default")
      (node (ref "SV1") (pin "7") (pinfunction "7_7") (pintype "passive"))
    )
    (net (code "145") (name "unconnected-(SV1-Pad8)") (class "Default")
      (node (ref "SV1") (pin "8") (pinfunction "8_8") (pintype "passive"))
    )
    (net (code "146") (name "unconnected-(USB-4-PadP$4)") (class "Default")
      (node (ref "USB") (pin "P$4") (pinfunction "4_P$4") (pintype "bidirectional"))
    )
    (net (code "147") (name "unconnected-(USB-P$2-PadSHIELD_2)") (class "Default")
      (node (ref "USB") (pin "SHIELD_2") (pinfunction "P$2_SHIELD_2") (pintype "bidirectional"))
    )
    (net (code "148") (name "unconnected-(USB-P$3-PadSHIELD_3)") (class "Default")
      (node (ref "USB") (pin "SHIELD_3") (pinfunction "P$3_SHIELD_3") (pintype "bidirectional"))
    )
  )
)
